# MyNixie.net
KiCad netlist of a schematic drawn in Altium Designer
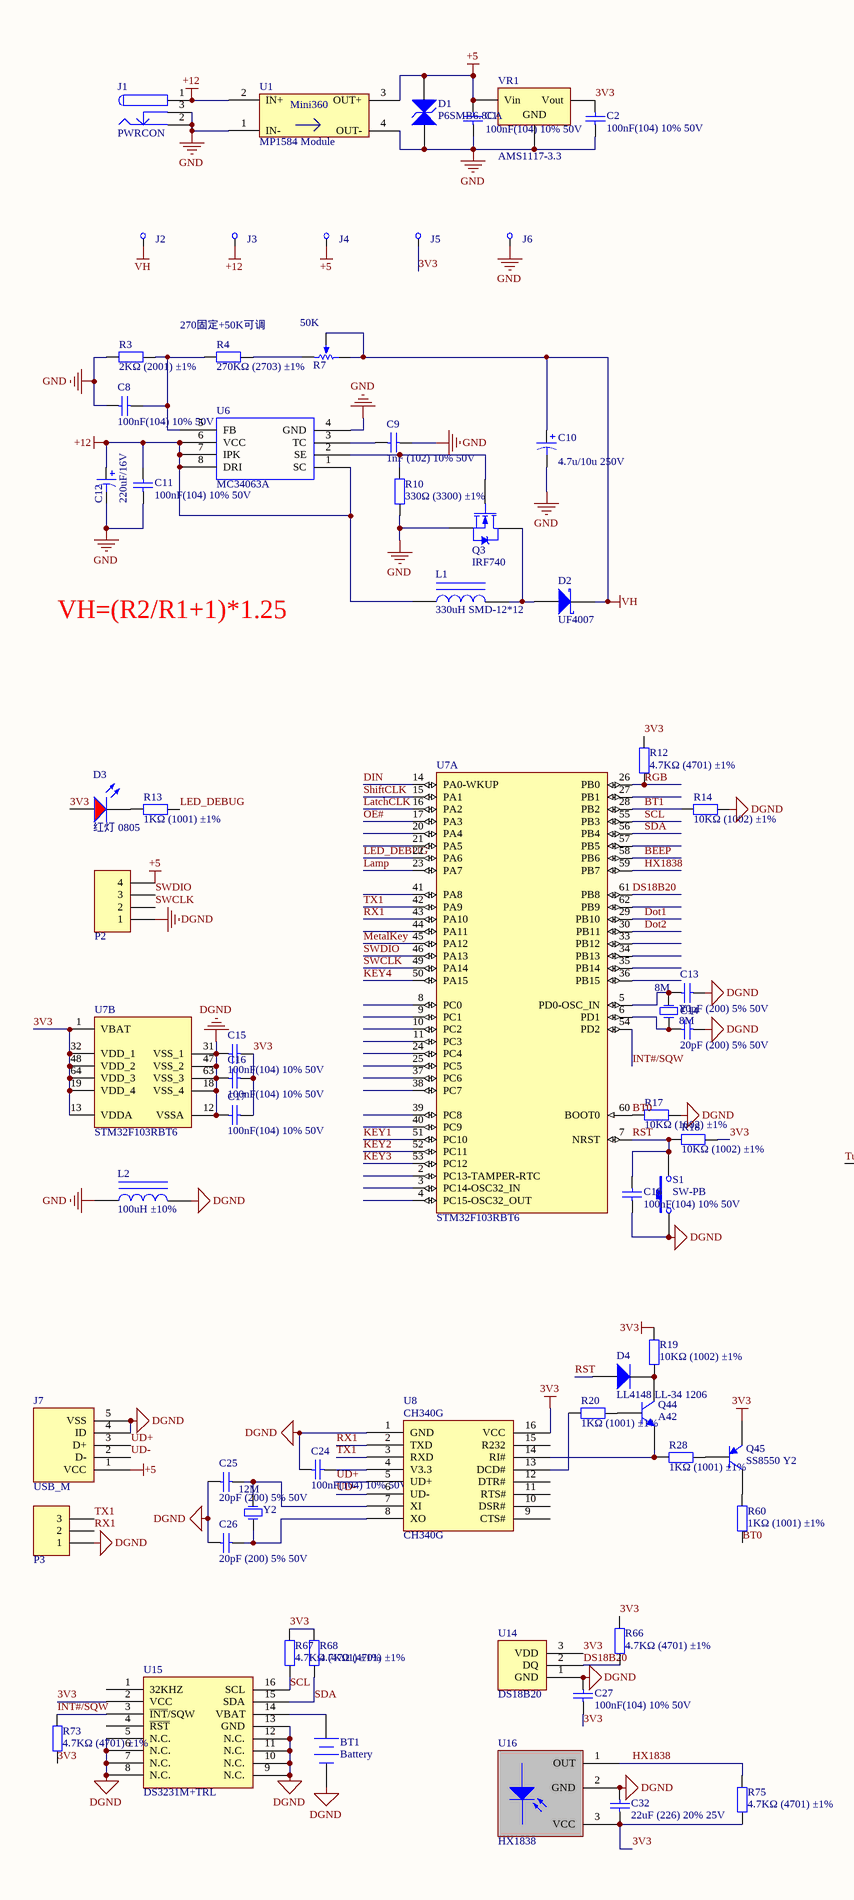
[diagram p0: MyNixie.SchDoc, left]
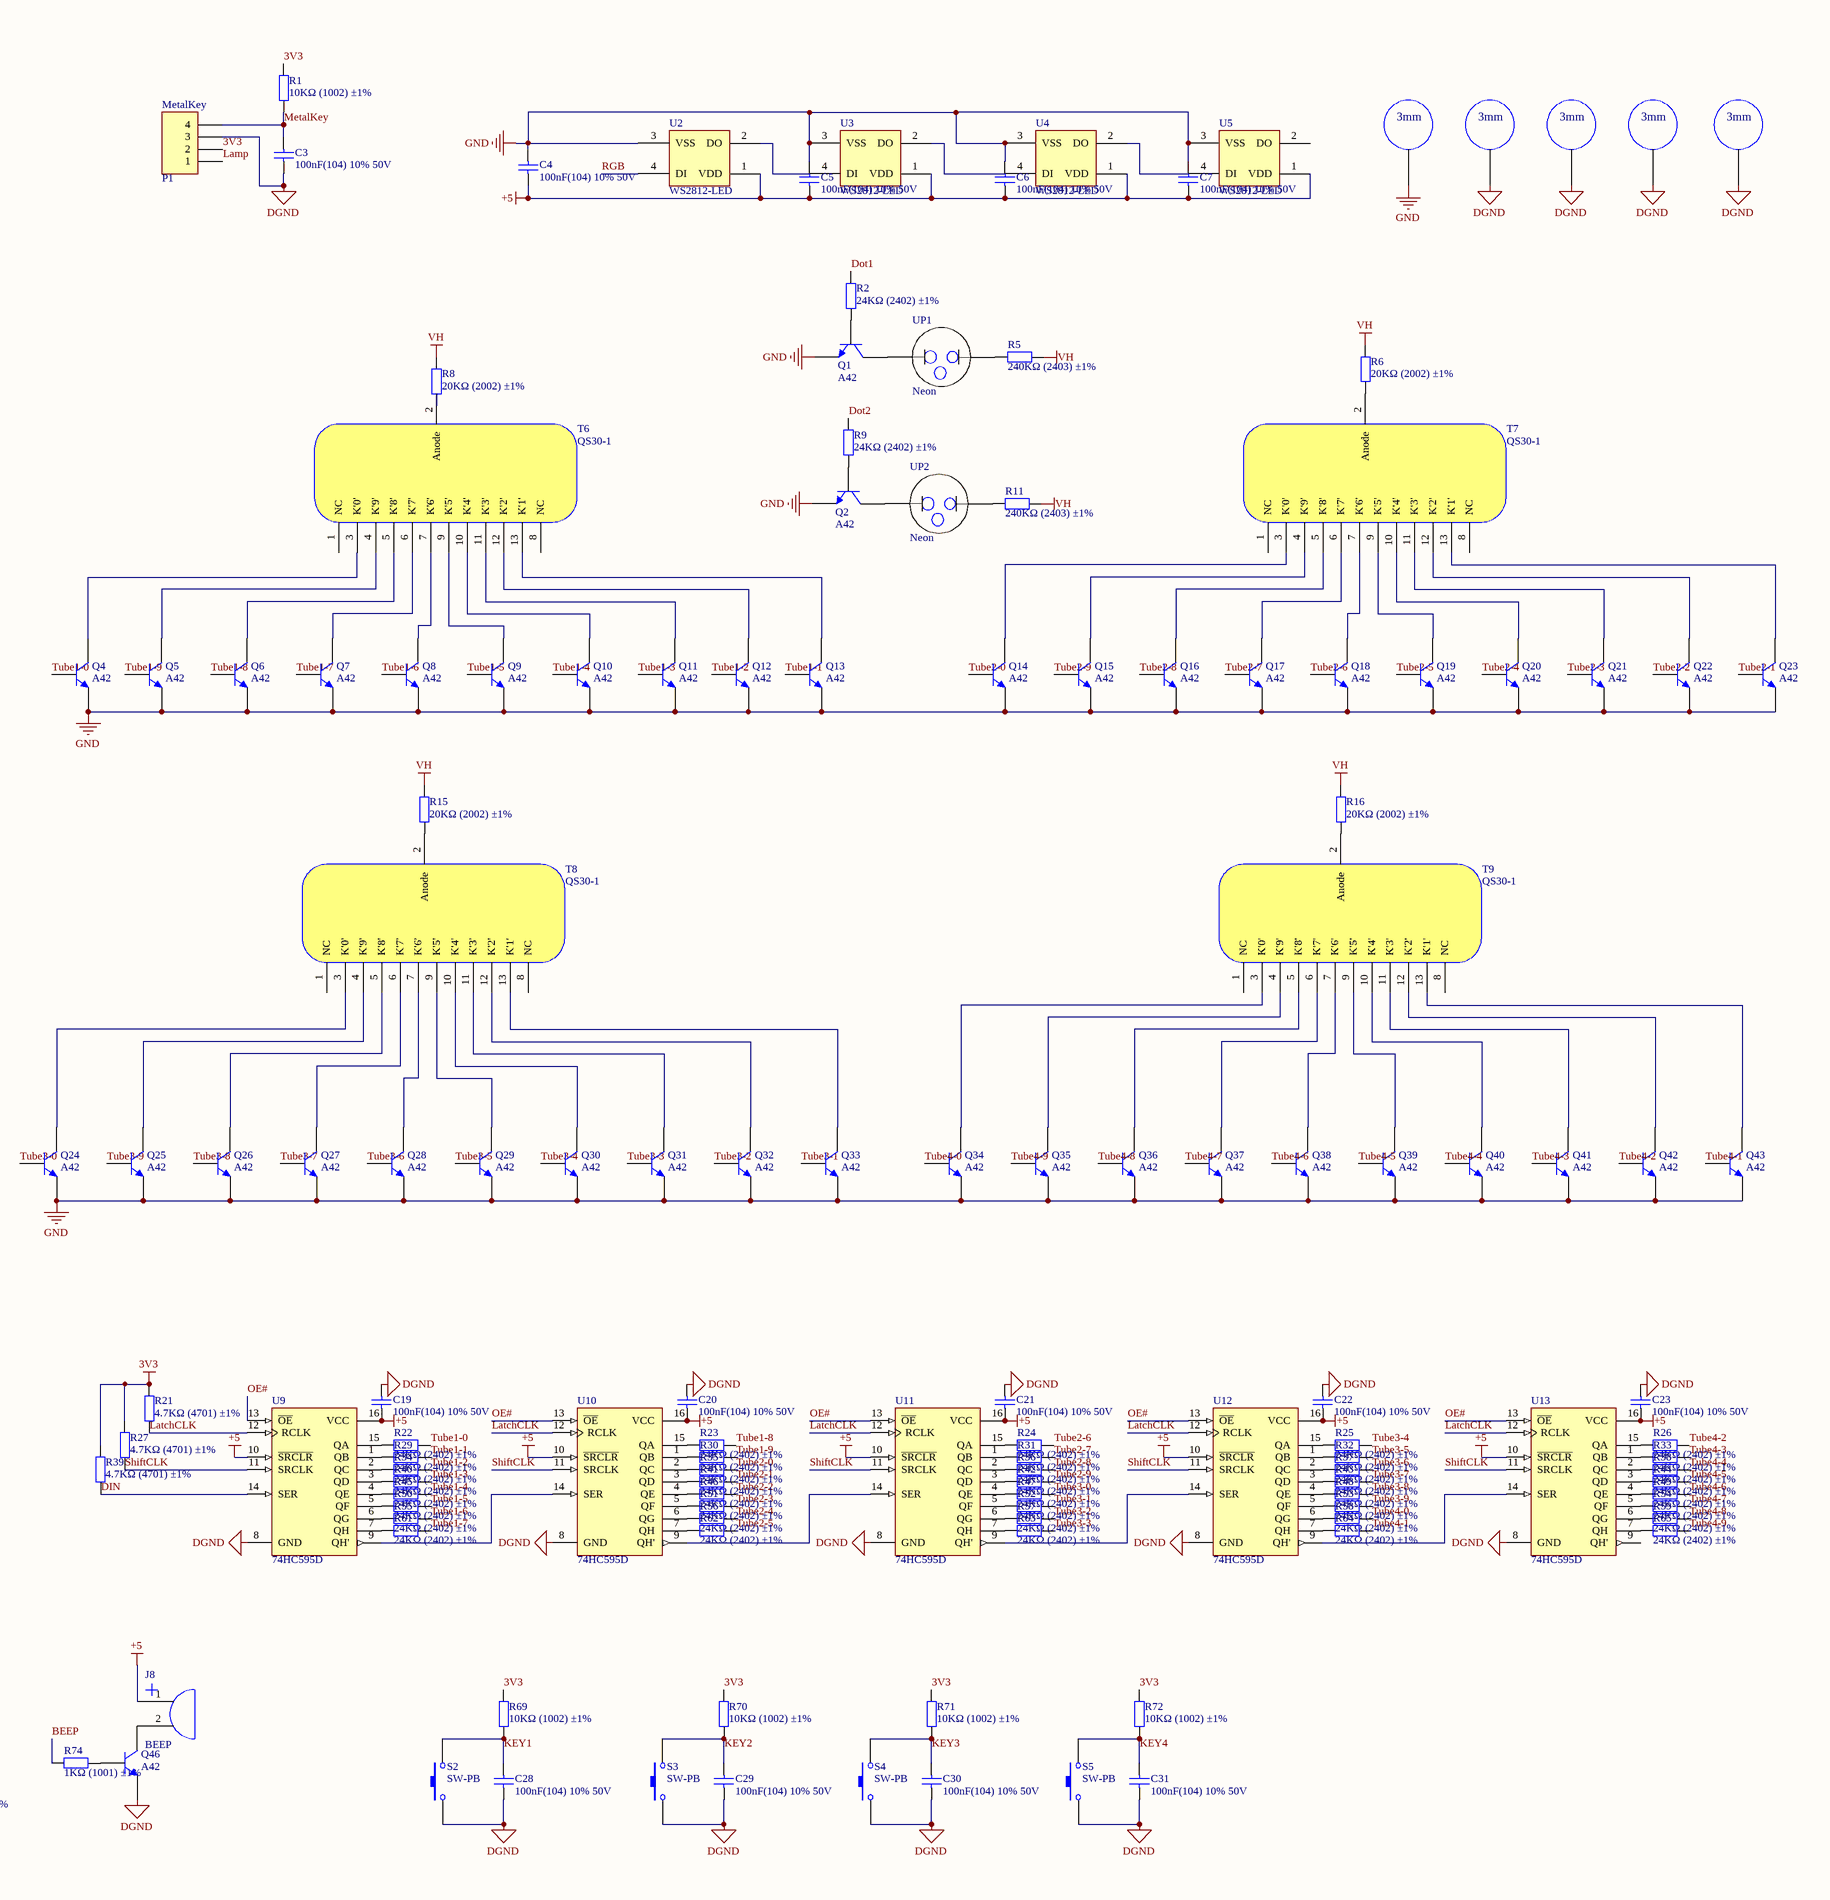
[diagram p1: MyNixie.SchDoc, right]

(export (version "E")
  (design (tool "Eeschema 10.0.6"))
  (components
    (comp (ref "BT1")
      (value "Battery")
      (footprint "CR1220")
      (description "备份电池")
      (fields (field (name "PUBLISHER") "Altium Limited"))
      (libsource (lib "fszhang") (part "Battery"))
    )
    (comp (ref "C1")
      (value "100nF(104) 10% 50V")
      (footprint "0805_C")
      (description "贴片电容")
      (libsource (lib "Miscellaneous Devices LC") (part "0805 100nF(104) 10% 50V"))
    )
    (comp (ref "C2")
      (value "100nF(104) 10% 50V")
      (footprint "0805_C")
      (description "贴片电容")
      (libsource (lib "Miscellaneous Devices LC") (part "0805 100nF(104) 10% 50V"))
    )
    (comp (ref "C3")
      (value "100nF(104) 10% 50V")
      (footprint "0805_C")
      (description "贴片电容")
      (libsource (lib "Miscellaneous Devices LC") (part "0805 100nF(104) 10% 50V"))
    )
    (comp (ref "C4")
      (value "100nF(104) 10% 50V")
      (footprint "0805_C")
      (description "贴片电容")
      (libsource (lib "Miscellaneous Devices LC") (part "0805 100nF(104) 10% 50V"))
    )
    (comp (ref "C5")
      (value "100nF(104) 10% 50V")
      (footprint "0805_C")
      (description "贴片电容")
      (libsource (lib "Miscellaneous Devices LC") (part "0805 100nF(104) 10% 50V"))
    )
    (comp (ref "C6")
      (value "100nF(104) 10% 50V")
      (footprint "0805_C")
      (description "贴片电容")
      (libsource (lib "Miscellaneous Devices LC") (part "0805 100nF(104) 10% 50V"))
    )
    (comp (ref "C7")
      (value "100nF(104) 10% 50V")
      (footprint "0805_C")
      (description "贴片电容")
      (libsource (lib "Miscellaneous Devices LC") (part "0805 100nF(104) 10% 50V"))
    )
    (comp (ref "C8")
      (value "100nF(104) 10% 50V")
      (footprint "0805_C")
      (description "贴片电容")
      (libsource (lib "Miscellaneous Devices LC") (part "0805 100nF(104) 10% 50V"))
    )
    (comp (ref "C9")
      (value "1nF (102) 10% 50V")
      (footprint "0805_C")
      (description "贴片电容")
      (libsource (lib "Miscellaneous Devices LC") (part "0805 1nF (102) 10% 50V"))
    )
    (comp (ref "C10")
      (value "4.7u/10u 250V")
      (footprint "C-RB-8")
      (description "极性电解电容")
      (fields (field (name "PUBLISHER") "Altium Limited"))
      (libsource (lib "Miscellaneous Devices") (part "Cap Pol1"))
    )
    (comp (ref "C11")
      (value "100nF(104) 10% 50V")
      (footprint "0805_C")
      (description "贴片电容")
      (libsource (lib "Miscellaneous Devices LC") (part "0805 100nF(104) 10% 50V"))
    )
    (comp (ref "C12")
      (value "220uF/16V")
      (footprint "C-RB-S6")
      (description "极性电解电容")
      (fields (field (name "PUBLISHER") "Altium Limited"))
      (libsource (lib "Miscellaneous Devices") (part "Cap Pol1"))
    )
    (comp (ref "C13")
      (value "20pF (200) 5% 50V")
      (footprint "0805_C")
      (description "贴片电容")
      (libsource (lib "Miscellaneous Devices LC") (part "0805 20pF (200) 5% 50V"))
    )
    (comp (ref "C14")
      (value "20pF (200) 5% 50V")
      (footprint "0805_C")
      (description "贴片电容")
      (libsource (lib "Miscellaneous Devices LC") (part "0805 20pF (200) 5% 50V"))
    )
    (comp (ref "C15")
      (value "100nF(104) 10% 50V")
      (footprint "0805_C")
      (description "贴片电容")
      (libsource (lib "Miscellaneous Devices LC") (part "0805 100nF(104) 10% 50V"))
    )
    (comp (ref "C16")
      (value "100nF(104) 10% 50V")
      (footprint "0805_C")
      (description "贴片电容")
      (libsource (lib "Miscellaneous Devices LC") (part "0805 100nF(104) 10% 50V"))
    )
    (comp (ref "C17")
      (value "100nF(104) 10% 50V")
      (footprint "0805_C")
      (description "贴片电容")
      (libsource (lib "Miscellaneous Devices LC") (part "0805 100nF(104) 10% 50V"))
    )
    (comp (ref "C18")
      (value "100nF(104) 10% 50V")
      (footprint "0805_C")
      (description "贴片电容")
      (libsource (lib "Miscellaneous Devices LC") (part "0805 100nF(104) 10% 50V"))
    )
    (comp (ref "C19")
      (value "100nF(104) 10% 50V")
      (footprint "0805_C")
      (description "贴片电容")
      (libsource (lib "Miscellaneous Devices LC") (part "0805 100nF(104) 10% 50V"))
    )
    (comp (ref "C20")
      (value "100nF(104) 10% 50V")
      (footprint "0805_C")
      (description "贴片电容")
      (libsource (lib "Miscellaneous Devices LC") (part "0805 100nF(104) 10% 50V"))
    )
    (comp (ref "C21")
      (value "100nF(104) 10% 50V")
      (footprint "0805_C")
      (description "贴片电容")
      (libsource (lib "Miscellaneous Devices LC") (part "0805 100nF(104) 10% 50V"))
    )
    (comp (ref "C22")
      (value "100nF(104) 10% 50V")
      (footprint "0805_C")
      (description "贴片电容")
      (libsource (lib "Miscellaneous Devices LC") (part "0805 100nF(104) 10% 50V"))
    )
    (comp (ref "C23")
      (value "100nF(104) 10% 50V")
      (footprint "0805_C")
      (description "贴片电容")
      (libsource (lib "Miscellaneous Devices LC") (part "0805 100nF(104) 10% 50V"))
    )
    (comp (ref "C24")
      (value "100nF(104) 10% 50V")
      (footprint "0805_C")
      (description "贴片电容")
      (libsource (lib "Miscellaneous Devices LC") (part "0805 100nF(104) 10% 50V"))
    )
    (comp (ref "C25")
      (value "20pF (200) 5% 50V")
      (footprint "0805_C")
      (description "贴片电容")
      (libsource (lib "Miscellaneous Devices LC") (part "0805 20pF (200) 5% 50V"))
    )
    (comp (ref "C26")
      (value "20pF (200) 5% 50V")
      (footprint "0805_C")
      (description "贴片电容")
      (libsource (lib "Miscellaneous Devices LC") (part "0805 20pF (200) 5% 50V"))
    )
    (comp (ref "C27")
      (value "100nF(104) 10% 50V")
      (footprint "0805_C")
      (description "贴片电容")
      (libsource (lib "Miscellaneous Devices LC") (part "0805 100nF(104) 10% 50V"))
    )
    (comp (ref "C28")
      (value "100nF(104) 10% 50V")
      (footprint "0805_C")
      (description "贴片电容")
      (libsource (lib "Miscellaneous Devices LC") (part "0805 100nF(104) 10% 50V"))
    )
    (comp (ref "C29")
      (value "100nF(104) 10% 50V")
      (footprint "0805_C")
      (description "贴片电容")
      (libsource (lib "Miscellaneous Devices LC") (part "0805 100nF(104) 10% 50V"))
    )
    (comp (ref "C30")
      (value "100nF(104) 10% 50V")
      (footprint "0805_C")
      (description "贴片电容")
      (libsource (lib "Miscellaneous Devices LC") (part "0805 100nF(104) 10% 50V"))
    )
    (comp (ref "C31")
      (value "100nF(104) 10% 50V")
      (footprint "0805_C")
      (description "贴片电容")
      (libsource (lib "Miscellaneous Devices LC") (part "0805 100nF(104) 10% 50V"))
    )
    (comp (ref "C32")
      (value "22uF (226) 20% 25V")
      (footprint "0805_C")
      (description "贴片电容")
      (libsource (lib "Miscellaneous Devices LC") (part "0805 22uF (226) 20% 25V"))
    )
    (comp (ref "D1")
      (value "P6SMB6.8CA")
      (footprint "SMB(DO-214AA)_S1")
      (description "TVS")
      (libsource (lib "Miscellaneous Devices LC") (part "SMB/DO-214AA P6SMB6.8CA"))
    )
    (comp (ref "D2")
      (value "UF4007")
      (footprint "SMA(DO-214AC)_S1")
      (description "Schottky Diode")
      (fields (field (name "PUBLISHER") "Altium Limited"))
      (libsource (lib "Miscellaneous Devices") (part "D Schottky"))
    )
    (comp (ref "D3")
      (value "红灯 0805")
      (footprint "0805_LED_S1")
      (description "发光二极管")
      (libsource (lib "Miscellaneous Devices LC") (part "0805 红灯"))
    )
    (comp (ref "D4")
      (value "LL4148 LL-34 1206")
      (footprint "LL-34")
      (description "开关二极管")
      (libsource (lib "Miscellaneous Devices LC") (part "LL-34 LL4148 LL-34 1206"))
    )
    (comp (ref "J1")
      (value "PWRCON")
      (footprint "DC-005")
      (description "直流电源端子")
      (fields (field (name "PUBLISHER") "Altium Limited"))
      (libsource (lib "fszhang") (part "PWRCON"))
    )
    (comp (ref "J2")
      (value "CHECK")
      (footprint "CHECK-B")
      (description "测试点")
      (libsource (lib "fszhang") (part "CHECK"))
    )
    (comp (ref "J3")
      (value "CHECK")
      (footprint "CHECK-B")
      (description "测试点")
      (libsource (lib "fszhang") (part "CHECK"))
    )
    (comp (ref "J4")
      (value "CHECK")
      (footprint "CHECK-B")
      (description "测试点")
      (libsource (lib "fszhang") (part "CHECK"))
    )
    (comp (ref "J5")
      (value "CHECK")
      (footprint "CHECK-B")
      (description "测试点")
      (libsource (lib "fszhang") (part "CHECK"))
    )
    (comp (ref "J6")
      (value "CHECK")
      (footprint "CHECK-B")
      (description "测试点")
      (libsource (lib "fszhang") (part "CHECK"))
    )
    (comp (ref "J7")
      (value "USB_M")
      (footprint "USB_MICRO")
      (description "MicroUSB接口")
      (libsource (lib "fszhang") (part "USB_M"))
    )
    (comp (ref "J8")
      (value "BEEP")
      (footprint "Beep-12095")
      (description "蜂鸣器")
      (libsource (lib "fszhang") (part "BEEP"))
    )
    (comp (ref "L1")
      (value "330uH SMD-12*12")
      (footprint "L-SMD-12")
      (description "Magnetic-Core Inductor")
      (fields (field (name "PUBLISHER") "Altium Limited"))
      (libsource (lib "Miscellaneous Devices") (part "Inductor Iron"))
    )
    (comp (ref "L2")
      (value "100uH ±10%")
      (footprint "0805_L")
      (description "贴片电感")
      (libsource (lib "Miscellaneous Devices LC") (part "0805 100uH 10%"))
    )
    (comp (ref "P1")
      (value "MetalKey")
      (footprint "HDR4X1_A")
      (description "接插件")
      (fields (field (name "PUBLISHER") "Altium Limited"))
      (libsource (lib "fszhang") (part "Header 4"))
    )
    (comp (ref "P2")
      (value "Header 4")
      (footprint "HDR4X1_A")
      (description "接插件")
      (fields (field (name "PUBLISHER") "Altium Limited"))
      (libsource (lib "fszhang") (part "Header 4"))
    )
    (comp (ref "P3")
      (value "Header 3")
      (footprint "HDR3X1_A")
      (description "接插件")
      (fields (field (name "PUBLISHER") "Altium Limited"))
      (libsource (lib "fszhang") (part "Header 3"))
    )
    (comp (ref "Q1")
      (value "A42")
      (footprint "SOT-23(SOT-23-3)")
      (description "三极管")
      (libsource (lib "Miscellaneous Devices LC") (part "SOT-23 SS8050 Y1"))
    )
    (comp (ref "Q2")
      (value "A42")
      (footprint "SOT-23(SOT-23-3)")
      (description "三极管")
      (libsource (lib "Miscellaneous Devices LC") (part "SOT-23 SS8050 Y1"))
    )
    (comp (ref "Q3")
      (value "IRF740")
      (footprint "Miscellaneous Devices LC:TO-263-2")
      (description "N-Channel Power MOSFET")
      (fields (field (name "PUBLISHER") "Altium Limited"))
      (libsource (lib "Miscellaneous Devices") (part "NMOS-2"))
    )
    (comp (ref "Q4")
      (value "A42")
      (footprint "SOT-23(SOT-23-3)")
      (description "三极管")
      (libsource (lib "Miscellaneous Devices LC") (part "SOT-23 SS8050 Y1"))
    )
    (comp (ref "Q5")
      (value "A42")
      (footprint "SOT-23(SOT-23-3)")
      (description "三极管")
      (libsource (lib "Miscellaneous Devices LC") (part "SOT-23 SS8050 Y1"))
    )
    (comp (ref "Q6")
      (value "A42")
      (footprint "SOT-23(SOT-23-3)")
      (description "三极管")
      (libsource (lib "Miscellaneous Devices LC") (part "SOT-23 SS8050 Y1"))
    )
    (comp (ref "Q7")
      (value "A42")
      (footprint "SOT-23(SOT-23-3)")
      (description "三极管")
      (libsource (lib "Miscellaneous Devices LC") (part "SOT-23 SS8050 Y1"))
    )
    (comp (ref "Q8")
      (value "A42")
      (footprint "SOT-23(SOT-23-3)")
      (description "三极管")
      (libsource (lib "Miscellaneous Devices LC") (part "SOT-23 SS8050 Y1"))
    )
    (comp (ref "Q9")
      (value "A42")
      (footprint "SOT-23(SOT-23-3)")
      (description "三极管")
      (libsource (lib "Miscellaneous Devices LC") (part "SOT-23 SS8050 Y1"))
    )
    (comp (ref "Q10")
      (value "A42")
      (footprint "SOT-23(SOT-23-3)")
      (description "三极管")
      (libsource (lib "Miscellaneous Devices LC") (part "SOT-23 SS8050 Y1"))
    )
    (comp (ref "Q11")
      (value "A42")
      (footprint "SOT-23(SOT-23-3)")
      (description "三极管")
      (libsource (lib "Miscellaneous Devices LC") (part "SOT-23 SS8050 Y1"))
    )
    (comp (ref "Q12")
      (value "A42")
      (footprint "SOT-23(SOT-23-3)")
      (description "三极管")
      (libsource (lib "Miscellaneous Devices LC") (part "SOT-23 SS8050 Y1"))
    )
    (comp (ref "Q13")
      (value "A42")
      (footprint "SOT-23(SOT-23-3)")
      (description "三极管")
      (libsource (lib "Miscellaneous Devices LC") (part "SOT-23 SS8050 Y1"))
    )
    (comp (ref "Q14")
      (value "A42")
      (footprint "SOT-23(SOT-23-3)")
      (description "三极管")
      (libsource (lib "Miscellaneous Devices LC") (part "SOT-23 SS8050 Y1"))
    )
    (comp (ref "Q15")
      (value "A42")
      (footprint "SOT-23(SOT-23-3)")
      (description "三极管")
      (libsource (lib "Miscellaneous Devices LC") (part "SOT-23 SS8050 Y1"))
    )
    (comp (ref "Q16")
      (value "A42")
      (footprint "SOT-23(SOT-23-3)")
      (description "三极管")
      (libsource (lib "Miscellaneous Devices LC") (part "SOT-23 SS8050 Y1"))
    )
    (comp (ref "Q17")
      (value "A42")
      (footprint "SOT-23(SOT-23-3)")
      (description "三极管")
      (libsource (lib "Miscellaneous Devices LC") (part "SOT-23 SS8050 Y1"))
    )
    (comp (ref "Q18")
      (value "A42")
      (footprint "SOT-23(SOT-23-3)")
      (description "三极管")
      (libsource (lib "Miscellaneous Devices LC") (part "SOT-23 SS8050 Y1"))
    )
    (comp (ref "Q19")
      (value "A42")
      (footprint "SOT-23(SOT-23-3)")
      (description "三极管")
      (libsource (lib "Miscellaneous Devices LC") (part "SOT-23 SS8050 Y1"))
    )
    (comp (ref "Q20")
      (value "A42")
      (footprint "SOT-23(SOT-23-3)")
      (description "三极管")
      (libsource (lib "Miscellaneous Devices LC") (part "SOT-23 SS8050 Y1"))
    )
    (comp (ref "Q21")
      (value "A42")
      (footprint "SOT-23(SOT-23-3)")
      (description "三极管")
      (libsource (lib "Miscellaneous Devices LC") (part "SOT-23 SS8050 Y1"))
    )
    (comp (ref "Q22")
      (value "A42")
      (footprint "SOT-23(SOT-23-3)")
      (description "三极管")
      (libsource (lib "Miscellaneous Devices LC") (part "SOT-23 SS8050 Y1"))
    )
    (comp (ref "Q23")
      (value "A42")
      (footprint "SOT-23(SOT-23-3)")
      (description "三极管")
      (libsource (lib "Miscellaneous Devices LC") (part "SOT-23 SS8050 Y1"))
    )
    (comp (ref "Q24")
      (value "A42")
      (footprint "SOT-23(SOT-23-3)")
      (description "三极管")
      (libsource (lib "Miscellaneous Devices LC") (part "SOT-23 SS8050 Y1"))
    )
    (comp (ref "Q25")
      (value "A42")
      (footprint "SOT-23(SOT-23-3)")
      (description "三极管")
      (libsource (lib "Miscellaneous Devices LC") (part "SOT-23 SS8050 Y1"))
    )
    (comp (ref "Q26")
      (value "A42")
      (footprint "SOT-23(SOT-23-3)")
      (description "三极管")
      (libsource (lib "Miscellaneous Devices LC") (part "SOT-23 SS8050 Y1"))
    )
    (comp (ref "Q27")
      (value "A42")
      (footprint "SOT-23(SOT-23-3)")
      (description "三极管")
      (libsource (lib "Miscellaneous Devices LC") (part "SOT-23 SS8050 Y1"))
    )
    (comp (ref "Q28")
      (value "A42")
      (footprint "SOT-23(SOT-23-3)")
      (description "三极管")
      (libsource (lib "Miscellaneous Devices LC") (part "SOT-23 SS8050 Y1"))
    )
    (comp (ref "Q29")
      (value "A42")
      (footprint "SOT-23(SOT-23-3)")
      (description "三极管")
      (libsource (lib "Miscellaneous Devices LC") (part "SOT-23 SS8050 Y1"))
    )
    (comp (ref "Q30")
      (value "A42")
      (footprint "SOT-23(SOT-23-3)")
      (description "三极管")
      (libsource (lib "Miscellaneous Devices LC") (part "SOT-23 SS8050 Y1"))
    )
    (comp (ref "Q31")
      (value "A42")
      (footprint "SOT-23(SOT-23-3)")
      (description "三极管")
      (libsource (lib "Miscellaneous Devices LC") (part "SOT-23 SS8050 Y1"))
    )
    (comp (ref "Q32")
      (value "A42")
      (footprint "SOT-23(SOT-23-3)")
      (description "三极管")
      (libsource (lib "Miscellaneous Devices LC") (part "SOT-23 SS8050 Y1"))
    )
    (comp (ref "Q33")
      (value "A42")
      (footprint "SOT-23(SOT-23-3)")
      (description "三极管")
      (libsource (lib "Miscellaneous Devices LC") (part "SOT-23 SS8050 Y1"))
    )
    (comp (ref "Q34")
      (value "A42")
      (footprint "SOT-23(SOT-23-3)")
      (description "三极管")
      (libsource (lib "Miscellaneous Devices LC") (part "SOT-23 SS8050 Y1"))
    )
    (comp (ref "Q35")
      (value "A42")
      (footprint "SOT-23(SOT-23-3)")
      (description "三极管")
      (libsource (lib "Miscellaneous Devices LC") (part "SOT-23 SS8050 Y1"))
    )
    (comp (ref "Q36")
      (value "A42")
      (footprint "SOT-23(SOT-23-3)")
      (description "三极管")
      (libsource (lib "Miscellaneous Devices LC") (part "SOT-23 SS8050 Y1"))
    )
    (comp (ref "Q37")
      (value "A42")
      (footprint "SOT-23(SOT-23-3)")
      (description "三极管")
      (libsource (lib "Miscellaneous Devices LC") (part "SOT-23 SS8050 Y1"))
    )
    (comp (ref "Q38")
      (value "A42")
      (footprint "SOT-23(SOT-23-3)")
      (description "三极管")
      (libsource (lib "Miscellaneous Devices LC") (part "SOT-23 SS8050 Y1"))
    )
    (comp (ref "Q39")
      (value "A42")
      (footprint "SOT-23(SOT-23-3)")
      (description "三极管")
      (libsource (lib "Miscellaneous Devices LC") (part "SOT-23 SS8050 Y1"))
    )
    (comp (ref "Q40")
      (value "A42")
      (footprint "SOT-23(SOT-23-3)")
      (description "三极管")
      (libsource (lib "Miscellaneous Devices LC") (part "SOT-23 SS8050 Y1"))
    )
    (comp (ref "Q41")
      (value "A42")
      (footprint "SOT-23(SOT-23-3)")
      (description "三极管")
      (libsource (lib "Miscellaneous Devices LC") (part "SOT-23 SS8050 Y1"))
    )
    (comp (ref "Q42")
      (value "A42")
      (footprint "SOT-23(SOT-23-3)")
      (description "三极管")
      (libsource (lib "Miscellaneous Devices LC") (part "SOT-23 SS8050 Y1"))
    )
    (comp (ref "Q43")
      (value "A42")
      (footprint "SOT-23(SOT-23-3)")
      (description "三极管")
      (libsource (lib "Miscellaneous Devices LC") (part "SOT-23 SS8050 Y1"))
    )
    (comp (ref "Q44")
      (value "A42")
      (footprint "SOT-23(SOT-23-3)")
      (description "三极管")
      (libsource (lib "Miscellaneous Devices LC") (part "SOT-23 SS8050 Y1"))
    )
    (comp (ref "Q45")
      (value "SS8550 Y2")
      (footprint "SOT-23(SOT-23-3)")
      (description "三极管")
      (libsource (lib "Miscellaneous Devices LC") (part "SOT-23 SS8550 Y2"))
    )
    (comp (ref "Q46")
      (value "A42")
      (footprint "SOT-23(SOT-23-3)")
      (description "三极管")
      (libsource (lib "Miscellaneous Devices LC") (part "SOT-23 SS8050 Y1"))
    )
    (comp (ref "R1")
      (value "10KΩ (1002) ±1%")
      (footprint "0805_R")
      (description "贴片电阻")
      (libsource (lib "Miscellaneous Devices LC") (part "0805 10KΩ (1002) 1%"))
    )
    (comp (ref "R2")
      (value "24KΩ (2402) ±1%")
      (footprint "0805_R")
      (description "贴片电阻")
      (libsource (lib "") (part "0805 24KΩ (2402) 1%_1"))
    )
    (comp (ref "R3")
      (value "2KΩ (2001) ±1%")
      (footprint "0805_R")
      (description "贴片电阻")
      (libsource (lib "Miscellaneous Devices LC") (part "0805 2KΩ (2001) 1%"))
    )
    (comp (ref "R4")
      (value "270KΩ (2703) ±1%")
      (footprint "0805_R")
      (description "贴片电阻")
      (libsource (lib "Miscellaneous Devices LC") (part "0805 270KΩ (2703) 1%"))
    )
    (comp (ref "R5")
      (value "240KΩ (2403) ±1%")
      (footprint "0805_R")
      (description "贴片电阻")
      (libsource (lib "Miscellaneous Devices LC") (part "0805 240KΩ (2403) 1%"))
    )
    (comp (ref "R6")
      (value "20KΩ (2002) ±1%")
      (footprint "0805_R")
      (description "贴片电阻")
      (libsource (lib "Miscellaneous Devices LC") (part "0805 20KΩ (2002) 1%"))
    )
    (comp (ref "R7")
      (value "50K")
      (footprint "VR_B1")
      (description "精密可调电阻")
      (fields (field (name "PUBLISHER") "Altium Limited"))
      (libsource (lib "fszhang") (part "RES-RPot"))
    )
    (comp (ref "R8")
      (value "20KΩ (2002) ±1%")
      (footprint "0805_R")
      (description "贴片电阻")
      (libsource (lib "Miscellaneous Devices LC") (part "0805 20KΩ (2002) 1%"))
    )
    (comp (ref "R9")
      (value "24KΩ (2402) ±1%")
      (footprint "0805_R")
      (description "贴片电阻")
      (libsource (lib "") (part "0805 24KΩ (2402) 1%_1"))
    )
    (comp (ref "R10")
      (value "330Ω (3300) ±1%")
      (footprint "0805_R")
      (description "贴片电阻")
      (libsource (lib "Miscellaneous Devices LC") (part "0805 330Ω (3300) 1%"))
    )
    (comp (ref "R11")
      (value "240KΩ (2403) ±1%")
      (footprint "0805_R")
      (description "贴片电阻")
      (libsource (lib "Miscellaneous Devices LC") (part "0805 240KΩ (2403) 1%"))
    )
    (comp (ref "R12")
      (value "4.7KΩ (4701) ±1%")
      (footprint "0805_R")
      (description "贴片电阻")
      (libsource (lib "Miscellaneous Devices LC") (part "0805 4.7KΩ (4701) 1%"))
    )
    (comp (ref "R13")
      (value "1KΩ (1001) ±1%")
      (footprint "0805_R")
      (description "贴片电阻")
      (libsource (lib "Miscellaneous Devices LC") (part "0805 1KΩ (1001) 1%"))
    )
    (comp (ref "R14")
      (value "10KΩ (1002) ±1%")
      (footprint "0805_R")
      (description "贴片电阻")
      (libsource (lib "") (part "0805 10KΩ (1002) 1%_1"))
    )
    (comp (ref "R15")
      (value "20KΩ (2002) ±1%")
      (footprint "0805_R")
      (description "贴片电阻")
      (libsource (lib "Miscellaneous Devices LC") (part "0805 20KΩ (2002) 1%"))
    )
    (comp (ref "R16")
      (value "20KΩ (2002) ±1%")
      (footprint "0805_R")
      (description "贴片电阻")
      (libsource (lib "Miscellaneous Devices LC") (part "0805 20KΩ (2002) 1%"))
    )
    (comp (ref "R17")
      (value "10KΩ (1002) ±1%")
      (footprint "0805_R")
      (description "贴片电阻")
      (libsource (lib "") (part "0805 10KΩ (1002) 1%_1"))
    )
    (comp (ref "R18")
      (value "10KΩ (1002) ±1%")
      (footprint "0805_R")
      (description "贴片电阻")
      (libsource (lib "") (part "0805 10KΩ (1002) 1%_1"))
    )
    (comp (ref "R19")
      (value "10KΩ (1002) ±1%")
      (footprint "0805_R")
      (description "贴片电阻")
      (libsource (lib "") (part "0805 10KΩ (1002) 1%_2"))
    )
    (comp (ref "R20")
      (value "1KΩ (1001) ±1%")
      (footprint "0805_R")
      (description "贴片电阻")
      (libsource (lib "Miscellaneous Devices LC") (part "0805 1KΩ (1001) 1%"))
    )
    (comp (ref "R21")
      (value "4.7KΩ (4701) ±1%")
      (footprint "0805_R")
      (description "贴片电阻")
      (libsource (lib "") (part "0805 4.7KΩ (4701) 1%_1"))
    )
    (comp (ref "R22")
      (value "24KΩ (2402) ±1%")
      (footprint "0805_R")
      (description "贴片电阻")
      (libsource (lib "Miscellaneous Devices LC") (part "0805 24KΩ (2402) 1%"))
    )
    (comp (ref "R23")
      (value "24KΩ (2402) ±1%")
      (footprint "0805_R")
      (description "贴片电阻")
      (libsource (lib "Miscellaneous Devices LC") (part "0805 24KΩ (2402) 1%"))
    )
    (comp (ref "R24")
      (value "24KΩ (2402) ±1%")
      (footprint "0805_R")
      (description "贴片电阻")
      (libsource (lib "Miscellaneous Devices LC") (part "0805 24KΩ (2402) 1%"))
    )
    (comp (ref "R25")
      (value "24KΩ (2402) ±1%")
      (footprint "0805_R")
      (description "贴片电阻")
      (libsource (lib "Miscellaneous Devices LC") (part "0805 24KΩ (2402) 1%"))
    )
    (comp (ref "R26")
      (value "24KΩ (2402) ±1%")
      (footprint "0805_R")
      (description "贴片电阻")
      (libsource (lib "Miscellaneous Devices LC") (part "0805 24KΩ (2402) 1%"))
    )
    (comp (ref "R27")
      (value "4.7KΩ (4701) ±1%")
      (footprint "0805_R")
      (description "贴片电阻")
      (libsource (lib "") (part "0805 4.7KΩ (4701) 1%_1"))
    )
    (comp (ref "R28")
      (value "1KΩ (1001) ±1%")
      (footprint "0805_R")
      (description "贴片电阻")
      (libsource (lib "Miscellaneous Devices LC") (part "0805 1KΩ (1001) 1%"))
    )
    (comp (ref "R29")
      (value "24KΩ (2402) ±1%")
      (footprint "0805_R")
      (description "贴片电阻")
      (libsource (lib "Miscellaneous Devices LC") (part "0805 24KΩ (2402) 1%"))
    )
    (comp (ref "R30")
      (value "24KΩ (2402) ±1%")
      (footprint "0805_R")
      (description "贴片电阻")
      (libsource (lib "Miscellaneous Devices LC") (part "0805 24KΩ (2402) 1%"))
    )
    (comp (ref "R31")
      (value "24KΩ (2402) ±1%")
      (footprint "0805_R")
      (description "贴片电阻")
      (libsource (lib "Miscellaneous Devices LC") (part "0805 24KΩ (2402) 1%"))
    )
    (comp (ref "R32")
      (value "24KΩ (2402) ±1%")
      (footprint "0805_R")
      (description "贴片电阻")
      (libsource (lib "Miscellaneous Devices LC") (part "0805 24KΩ (2402) 1%"))
    )
    (comp (ref "R33")
      (value "24KΩ (2402) ±1%")
      (footprint "0805_R")
      (description "贴片电阻")
      (libsource (lib "Miscellaneous Devices LC") (part "0805 24KΩ (2402) 1%"))
    )
    (comp (ref "R34")
      (value "24KΩ (2402) ±1%")
      (footprint "0805_R")
      (description "贴片电阻")
      (libsource (lib "Miscellaneous Devices LC") (part "0805 24KΩ (2402) 1%"))
    )
    (comp (ref "R35")
      (value "24KΩ (2402) ±1%")
      (footprint "0805_R")
      (description "贴片电阻")
      (libsource (lib "Miscellaneous Devices LC") (part "0805 24KΩ (2402) 1%"))
    )
    (comp (ref "R36")
      (value "24KΩ (2402) ±1%")
      (footprint "0805_R")
      (description "贴片电阻")
      (libsource (lib "Miscellaneous Devices LC") (part "0805 24KΩ (2402) 1%"))
    )
    (comp (ref "R37")
      (value "24KΩ (2402) ±1%")
      (footprint "0805_R")
      (description "贴片电阻")
      (libsource (lib "Miscellaneous Devices LC") (part "0805 24KΩ (2402) 1%"))
    )
    (comp (ref "R38")
      (value "24KΩ (2402) ±1%")
      (footprint "0805_R")
      (description "贴片电阻")
      (libsource (lib "Miscellaneous Devices LC") (part "0805 24KΩ (2402) 1%"))
    )
    (comp (ref "R39")
      (value "4.7KΩ (4701) ±1%")
      (footprint "0805_R")
      (description "贴片电阻")
      (libsource (lib "") (part "0805 4.7KΩ (4701) 1%_1"))
    )
    (comp (ref "R40")
      (value "24KΩ (2402) ±1%")
      (footprint "0805_R")
      (description "贴片电阻")
      (libsource (lib "Miscellaneous Devices LC") (part "0805 24KΩ (2402) 1%"))
    )
    (comp (ref "R41")
      (value "24KΩ (2402) ±1%")
      (footprint "0805_R")
      (description "贴片电阻")
      (libsource (lib "Miscellaneous Devices LC") (part "0805 24KΩ (2402) 1%"))
    )
    (comp (ref "R42")
      (value "24KΩ (2402) ±1%")
      (footprint "0805_R")
      (description "贴片电阻")
      (libsource (lib "Miscellaneous Devices LC") (part "0805 24KΩ (2402) 1%"))
    )
    (comp (ref "R43")
      (value "24KΩ (2402) ±1%")
      (footprint "0805_R")
      (description "贴片电阻")
      (libsource (lib "Miscellaneous Devices LC") (part "0805 24KΩ (2402) 1%"))
    )
    (comp (ref "R44")
      (value "24KΩ (2402) ±1%")
      (footprint "0805_R")
      (description "贴片电阻")
      (libsource (lib "Miscellaneous Devices LC") (part "0805 24KΩ (2402) 1%"))
    )
    (comp (ref "R45")
      (value "24KΩ (2402) ±1%")
      (footprint "0805_R")
      (description "贴片电阻")
      (libsource (lib "Miscellaneous Devices LC") (part "0805 24KΩ (2402) 1%"))
    )
    (comp (ref "R46")
      (value "24KΩ (2402) ±1%")
      (footprint "0805_R")
      (description "贴片电阻")
      (libsource (lib "Miscellaneous Devices LC") (part "0805 24KΩ (2402) 1%"))
    )
    (comp (ref "R47")
      (value "24KΩ (2402) ±1%")
      (footprint "0805_R")
      (description "贴片电阻")
      (libsource (lib "Miscellaneous Devices LC") (part "0805 24KΩ (2402) 1%"))
    )
    (comp (ref "R48")
      (value "24KΩ (2402) ±1%")
      (footprint "0805_R")
      (description "贴片电阻")
      (libsource (lib "Miscellaneous Devices LC") (part "0805 24KΩ (2402) 1%"))
    )
    (comp (ref "R49")
      (value "24KΩ (2402) ±1%")
      (footprint "0805_R")
      (description "贴片电阻")
      (libsource (lib "Miscellaneous Devices LC") (part "0805 24KΩ (2402) 1%"))
    )
    (comp (ref "R50")
      (value "24KΩ (2402) ±1%")
      (footprint "0805_R")
      (description "贴片电阻")
      (libsource (lib "Miscellaneous Devices LC") (part "0805 24KΩ (2402) 1%"))
    )
    (comp (ref "R51")
      (value "24KΩ (2402) ±1%")
      (footprint "0805_R")
      (description "贴片电阻")
      (libsource (lib "Miscellaneous Devices LC") (part "0805 24KΩ (2402) 1%"))
    )
    (comp (ref "R52")
      (value "24KΩ (2402) ±1%")
      (footprint "0805_R")
      (description "贴片电阻")
      (libsource (lib "Miscellaneous Devices LC") (part "0805 24KΩ (2402) 1%"))
    )
    (comp (ref "R53")
      (value "24KΩ (2402) ±1%")
      (footprint "0805_R")
      (description "贴片电阻")
      (libsource (lib "Miscellaneous Devices LC") (part "0805 24KΩ (2402) 1%"))
    )
    (comp (ref "R54")
      (value "24KΩ (2402) ±1%")
      (footprint "0805_R")
      (description "贴片电阻")
      (libsource (lib "Miscellaneous Devices LC") (part "0805 24KΩ (2402) 1%"))
    )
    (comp (ref "R55")
      (value "24KΩ (2402) ±1%")
      (footprint "0805_R")
      (description "贴片电阻")
      (libsource (lib "Miscellaneous Devices LC") (part "0805 24KΩ (2402) 1%"))
    )
    (comp (ref "R56")
      (value "24KΩ (2402) ±1%")
      (footprint "0805_R")
      (description "贴片电阻")
      (libsource (lib "Miscellaneous Devices LC") (part "0805 24KΩ (2402) 1%"))
    )
    (comp (ref "R57")
      (value "24KΩ (2402) ±1%")
      (footprint "0805_R")
      (description "贴片电阻")
      (libsource (lib "Miscellaneous Devices LC") (part "0805 24KΩ (2402) 1%"))
    )
    (comp (ref "R58")
      (value "24KΩ (2402) ±1%")
      (footprint "0805_R")
      (description "贴片电阻")
      (libsource (lib "Miscellaneous Devices LC") (part "0805 24KΩ (2402) 1%"))
    )
    (comp (ref "R59")
      (value "24KΩ (2402) ±1%")
      (footprint "0805_R")
      (description "贴片电阻")
      (libsource (lib "Miscellaneous Devices LC") (part "0805 24KΩ (2402) 1%"))
    )
    (comp (ref "R60")
      (value "1KΩ (1001) ±1%")
      (footprint "0805_R")
      (description "贴片电阻")
      (libsource (lib "") (part "0805 1KΩ (1001) 1%_1"))
    )
    (comp (ref "R61")
      (value "24KΩ (2402) ±1%")
      (footprint "0805_R")
      (description "贴片电阻")
      (libsource (lib "Miscellaneous Devices LC") (part "0805 24KΩ (2402) 1%"))
    )
    (comp (ref "R62")
      (value "24KΩ (2402) ±1%")
      (footprint "0805_R")
      (description "贴片电阻")
      (libsource (lib "Miscellaneous Devices LC") (part "0805 24KΩ (2402) 1%"))
    )
    (comp (ref "R63")
      (value "24KΩ (2402) ±1%")
      (footprint "0805_R")
      (description "贴片电阻")
      (libsource (lib "Miscellaneous Devices LC") (part "0805 24KΩ (2402) 1%"))
    )
    (comp (ref "R64")
      (value "24KΩ (2402) ±1%")
      (footprint "0805_R")
      (description "贴片电阻")
      (libsource (lib "Miscellaneous Devices LC") (part "0805 24KΩ (2402) 1%"))
    )
    (comp (ref "R65")
      (value "24KΩ (2402) ±1%")
      (footprint "0805_R")
      (description "贴片电阻")
      (libsource (lib "Miscellaneous Devices LC") (part "0805 24KΩ (2402) 1%"))
    )
    (comp (ref "R66")
      (value "4.7KΩ (4701) ±1%")
      (footprint "0805_R")
      (description "贴片电阻")
      (libsource (lib "Miscellaneous Devices LC") (part "0805 4.7KΩ (4701) 1%"))
    )
    (comp (ref "R67")
      (value "4.7KΩ (4701) ±1%")
      (footprint "0805_R")
      (description "贴片电阻")
      (libsource (lib "Miscellaneous Devices LC") (part "0805 4.7KΩ (4701) 1%"))
    )
    (comp (ref "R68")
      (value "4.7KΩ (4701) ±1%")
      (footprint "0805_R")
      (description "贴片电阻")
      (libsource (lib "Miscellaneous Devices LC") (part "0805 4.7KΩ (4701) 1%"))
    )
    (comp (ref "R69")
      (value "10KΩ (1002) ±1%")
      (footprint "0805_R")
      (description "贴片电阻")
      (libsource (lib "Miscellaneous Devices LC") (part "0805 10KΩ (1002) 1%"))
    )
    (comp (ref "R70")
      (value "10KΩ (1002) ±1%")
      (footprint "0805_R")
      (description "贴片电阻")
      (libsource (lib "Miscellaneous Devices LC") (part "0805 10KΩ (1002) 1%"))
    )
    (comp (ref "R71")
      (value "10KΩ (1002) ±1%")
      (footprint "0805_R")
      (description "贴片电阻")
      (libsource (lib "Miscellaneous Devices LC") (part "0805 10KΩ (1002) 1%"))
    )
    (comp (ref "R72")
      (value "10KΩ (1002) ±1%")
      (footprint "0805_R")
      (description "贴片电阻")
      (libsource (lib "Miscellaneous Devices LC") (part "0805 10KΩ (1002) 1%"))
    )
    (comp (ref "R73")
      (value "4.7KΩ (4701) ±1%")
      (footprint "0805_R")
      (description "贴片电阻")
      (libsource (lib "Miscellaneous Devices LC") (part "0805 4.7KΩ (4701) 1%"))
    )
    (comp (ref "R74")
      (value "1KΩ (1001) ±1%")
      (footprint "0805_R")
      (description "贴片电阻")
      (libsource (lib "Miscellaneous Devices LC") (part "0805 1KΩ (1001) 1%"))
    )
    (comp (ref "R75")
      (value "4.7KΩ (4701) ±1%")
      (footprint "0805_R")
      (description "贴片电阻")
      (libsource (lib "Miscellaneous Devices LC") (part "0805 4.7KΩ (4701) 1%"))
    )
    (comp (ref "S1")
      (value "SW-PB")
      (footprint "SW_PB2_A1")
      (description "微动开关")
      (fields (field (name "PUBLISHER") "Altium Limited"))
      (libsource (lib "fszhang") (part "SW-PB"))
    )
    (comp (ref "S2")
      (value "SW-PB")
      (footprint "SW_PB2_A1")
      (description "微动开关")
      (fields (field (name "PUBLISHER") "Altium Limited"))
      (libsource (lib "fszhang") (part "SW-PB"))
    )
    (comp (ref "S3")
      (value "SW-PB")
      (footprint "SW_PB2_A1")
      (description "微动开关")
      (fields (field (name "PUBLISHER") "Altium Limited"))
      (libsource (lib "fszhang") (part "SW-PB"))
    )
    (comp (ref "S4")
      (value "SW-PB")
      (footprint "SW_PB2_A1")
      (description "微动开关")
      (fields (field (name "PUBLISHER") "Altium Limited"))
      (libsource (lib "fszhang") (part "SW-PB"))
    )
    (comp (ref "S5")
      (value "SW-PB")
      (footprint "SW_PB2_A1")
      (description "微动开关")
      (fields (field (name "PUBLISHER") "Altium Limited"))
      (libsource (lib "fszhang") (part "SW-PB"))
    )
    (comp (ref "T1") (value "M3铜柱螺丝孔") (footprint "螺丝孔-3mm") (libsource (lib "fszhang") (part "M3铜柱螺丝孔")))
    (comp (ref "T2") (value "M3铜柱螺丝孔") (footprint "螺丝孔-3mm") (libsource (lib "fszhang") (part "M3铜柱螺丝孔")))
    (comp (ref "T3") (value "M3铜柱螺丝孔") (footprint "螺丝孔-3mm") (libsource (lib "fszhang") (part "M3铜柱螺丝孔")))
    (comp (ref "T4") (value "M3铜柱螺丝孔") (footprint "螺丝孔-3mm") (libsource (lib "fszhang") (part "M3铜柱螺丝孔")))
    (comp (ref "T5") (value "M3铜柱螺丝孔") (footprint "螺丝孔-3mm") (libsource (lib "fszhang") (part "M3铜柱螺丝孔")))
    (comp (ref "T6")
      (value "QS30-1")
      (footprint "QS30-1")
      (description "南昌辉光管")
      (libsource (lib "fszhang") (part "QS30-1"))
    )
    (comp (ref "T7")
      (value "QS30-1")
      (footprint "QS30-1")
      (description "南昌辉光管")
      (libsource (lib "fszhang") (part "QS30-1"))
    )
    (comp (ref "T8")
      (value "QS30-1")
      (footprint "QS30-1")
      (description "南昌辉光管")
      (libsource (lib "fszhang") (part "QS30-1"))
    )
    (comp (ref "T9")
      (value "QS30-1")
      (footprint "QS30-1")
      (description "南昌辉光管")
      (libsource (lib "fszhang") (part "QS30-1"))
    )
    (comp (ref "U1")
      (value "MP1584 Module")
      (footprint "MP1584 Module")
      (libsource (lib "fszhang") (part "MP1584 Module"))
    )
    (comp (ref "U2")
      (value "WS2812-LED")
      (footprint "WS2812")
      (libsource (lib "fszhang") (part "WS2812-LED"))
    )
    (comp (ref "U3")
      (value "WS2812-LED")
      (footprint "WS2812")
      (libsource (lib "fszhang") (part "WS2812-LED"))
    )
    (comp (ref "U4")
      (value "WS2812-LED")
      (footprint "WS2812")
      (libsource (lib "fszhang") (part "WS2812-LED"))
    )
    (comp (ref "U5")
      (value "WS2812-LED")
      (footprint "WS2812")
      (libsource (lib "fszhang") (part "WS2812-LED"))
    )
    (comp (ref "U6")
      (value "MC34063A")
      (footprint "SOIC-8_150mil")
      (libsource (lib "NIXIEClock_SCHLib") (part "MC34063A"))
    )
    (comp (ref "U7")
      (value "STM32F103RBT6")
      (footprint "LQFP-64_10x10x05P")
      (description "ARM")
      (libsource (lib "Miscellaneous Devices LC") (part "STM32F103RBT6"))
    )
    (comp (ref "U8")
      (value "CH340G")
      (footprint "SOIC-16_150mil")
      (description "USB")
      (libsource (lib "Miscellaneous Devices LC") (part "CH340G_[C14267]"))
    )
    (comp (ref "U9")
      (value "74HC595D")
      (footprint "SOIC-16_150mil")
      (description "74系列逻辑芯片")
      (libsource (lib "Miscellaneous Devices LC") (part "74HC595D"))
    )
    (comp (ref "U10")
      (value "74HC595D")
      (footprint "SOIC-16_150mil")
      (description "74系列逻辑芯片")
      (libsource (lib "Miscellaneous Devices LC") (part "74HC595D"))
    )
    (comp (ref "U11")
      (value "74HC595D")
      (footprint "SOIC-16_150mil")
      (description "74系列逻辑芯片")
      (libsource (lib "Miscellaneous Devices LC") (part "74HC595D"))
    )
    (comp (ref "U12")
      (value "74HC595D")
      (footprint "SOIC-16_150mil")
      (description "74系列逻辑芯片")
      (libsource (lib "Miscellaneous Devices LC") (part "74HC595D"))
    )
    (comp (ref "U13")
      (value "74HC595D")
      (footprint "SOIC-16_150mil")
      (description "74系列逻辑芯片")
      (libsource (lib "Miscellaneous Devices LC") (part "74HC595D"))
    )
    (comp (ref "U14")
      (value "DS18B20")
      (footprint "TO-92A")
      (description "温度传感器")
      (libsource (lib "fszhang") (part "DS18B20"))
    )
    (comp (ref "U15")
      (value "DS3231M+TRL")
      (footprint "SOIC-16_300mil")
      (description "实时时钟")
      (libsource (lib "Miscellaneous Devices LC") (part "DS3231M+TRL"))
    )
    (comp (ref "U16")
      (value "HX1838")
      (footprint "HS0038B")
      (description "红外接收器")
      (libsource (lib "fszhang") (part "HS0038B"))
    )
    (comp (ref "UP1")
      (value "Neon")
      (footprint "Neon")
      (description "氖泡")
      (libsource (lib "fszhang") (part "Neon"))
    )
    (comp (ref "UP2")
      (value "Neon")
      (footprint "Neon")
      (description "氖泡")
      (libsource (lib "fszhang") (part "Neon"))
    )
    (comp (ref "VR1")
      (value "AMS1117-3.3")
      (footprint "SOT-223")
      (description "低压差线性稳压(LDO)")
      (libsource (lib "Miscellaneous Devices LC") (part "SOT-223 AMS1117-3.3"))
    )
    (comp (ref "Y1")
      (value "8M")
      (footprint "X-SM49")
      (description "晶振")
      (fields (field (name "ALTIUM_VALUE") "8M") (field (name "PUBLISHER") "Altium Limited"))
      (libsource (lib "fszhang") (part "XTAL"))
    )
    (comp (ref "Y2")
      (value "12M")
      (footprint "X-SM49")
      (description "晶振")
      (fields (field (name "PUBLISHER") "Altium Limited"))
      (libsource (lib "fszhang") (part "XTAL"))
    )
  )
  (nets
    (net (code "1") (name "+5") (class "Default")
      (node (ref "C1") (pin "2") (pinfunction "2_2") (pintype "passive"))
      (node (ref "C19") (pin "1") (pinfunction "1_1") (pintype "passive"))
      (node (ref "C20") (pin "1") (pinfunction "1_1") (pintype "passive"))
      (node (ref "C21") (pin "1") (pinfunction "1_1") (pintype "passive"))
      (node (ref "C22") (pin "1") (pinfunction "1_1") (pintype "passive"))
      (node (ref "C23") (pin "1") (pinfunction "1_1") (pintype "passive"))
      (node (ref "C4") (pin "1") (pinfunction "1_1") (pintype "passive"))
      (node (ref "C5") (pin "1") (pinfunction "1_1") (pintype "passive"))
      (node (ref "C6") (pin "1") (pinfunction "1_1") (pintype "passive"))
      (node (ref "C7") (pin "1") (pinfunction "1_1") (pintype "passive"))
      (node (ref "D1") (pin "1") (pinfunction "A_1") (pintype "passive"))
      (node (ref "J4") (pin "1") (pinfunction "1_1") (pintype "passive"))
      (node (ref "J7") (pin "1") (pinfunction "VCC_1") (pintype "passive"))
      (node (ref "J8") (pin "1") (pinfunction "0_1") (pintype "passive"))
      (node (ref "P2") (pin "4") (pinfunction "4_4") (pintype "passive"))
      (node (ref "U1") (pin "3") (pinfunction "OUT+_3") (pintype "passive"))
      (node (ref "U10") (pin "10") (pinfunction "~{SRCLR}_10") (pintype "input"))
      (node (ref "U10") (pin "16") (pinfunction "VCC_16") (pintype "power_in"))
      (node (ref "U11") (pin "10") (pinfunction "~{SRCLR}_10") (pintype "input"))
      (node (ref "U11") (pin "16") (pinfunction "VCC_16") (pintype "power_in"))
      (node (ref "U12") (pin "10") (pinfunction "~{SRCLR}_10") (pintype "input"))
      (node (ref "U12") (pin "16") (pinfunction "VCC_16") (pintype "power_in"))
      (node (ref "U13") (pin "10") (pinfunction "~{SRCLR}_10") (pintype "input"))
      (node (ref "U13") (pin "16") (pinfunction "VCC_16") (pintype "power_in"))
      (node (ref "U2") (pin "1") (pinfunction "VDD_1") (pintype "passive"))
      (node (ref "U3") (pin "1") (pinfunction "VDD_1") (pintype "passive"))
      (node (ref "U4") (pin "1") (pinfunction "VDD_1") (pintype "passive"))
      (node (ref "U5") (pin "1") (pinfunction "VDD_1") (pintype "passive"))
      (node (ref "U9") (pin "10") (pinfunction "~{SRCLR}_10") (pintype "input"))
      (node (ref "U9") (pin "16") (pinfunction "VCC_16") (pintype "power_in"))
      (node (ref "VR1") (pin "3") (pinfunction "Vin_3") (pintype "passive"))
    )
    (net (code "2") (name "+12") (class "Default")
      (node (ref "C11") (pin "2") (pinfunction "2_2") (pintype "passive"))
      (node (ref "C12") (pin "1") (pinfunction "1_1") (pintype "passive"))
      (node (ref "J1") (pin "1") (pinfunction "1_1") (pintype "power_in"))
      (node (ref "J3") (pin "1") (pinfunction "1_1") (pintype "passive"))
      (node (ref "L1") (pin "1") (pinfunction "1_1") (pintype "passive"))
      (node (ref "U1") (pin "2") (pinfunction "IN+_2") (pintype "passive"))
      (node (ref "U6") (pin "1") (pinfunction "SC_1") (pintype "passive"))
      (node (ref "U6") (pin "6") (pinfunction "VCC_6") (pintype "passive"))
      (node (ref "U6") (pin "7") (pinfunction "IPK_7") (pintype "passive"))
      (node (ref "U6") (pin "8") (pinfunction "DRI_8") (pintype "passive"))
    )
    (net (code "3") (name "/BEEP") (class "Default")
      (node (ref "R74") (pin "1") (pinfunction "1_1") (pintype "passive"))
      (node (ref "U7") (pin "58") (pinfunction "PB6_58") (pintype "bidirectional"))
    )
    (net (code "4") (name "/BT0") (class "Default")
      (node (ref "R17") (pin "2") (pinfunction "2_2") (pintype "passive"))
      (node (ref "R60") (pin "1") (pinfunction "1_1") (pintype "passive"))
      (node (ref "U7") (pin "60") (pinfunction "BOOT0_60") (pintype "input"))
    )
    (net (code "5") (name "/BT1") (class "Default")
      (node (ref "R14") (pin "2") (pinfunction "2_2") (pintype "passive"))
      (node (ref "U7") (pin "28") (pinfunction "PB2_28") (pintype "bidirectional"))
    )
    (net (code "6") (name "/DIN") (class "Default")
      (node (ref "R39") (pin "2") (pinfunction "2_2") (pintype "passive"))
      (node (ref "U7") (pin "14") (pinfunction "PA0-WKUP_14") (pintype "bidirectional"))
      (node (ref "U9") (pin "14") (pinfunction "SER_14") (pintype "input"))
    )
    (net (code "7") (name "/DS18B20") (class "Default")
      (node (ref "R66") (pin "1") (pinfunction "1_1") (pintype "passive"))
      (node (ref "U14") (pin "2") (pinfunction "DQ_2") (pintype "passive"))
      (node (ref "U7") (pin "61") (pinfunction "PB8_61") (pintype "bidirectional"))
    )
    (net (code "8") (name "/Dot1") (class "Default")
      (node (ref "R2") (pin "2") (pinfunction "2_2") (pintype "passive"))
      (node (ref "U7") (pin "29") (pinfunction "PB10_29") (pintype "bidirectional"))
    )
    (net (code "9") (name "/Dot2") (class "Default")
      (node (ref "R9") (pin "2") (pinfunction "2_2") (pintype "passive"))
      (node (ref "U7") (pin "30") (pinfunction "PB11_30") (pintype "bidirectional"))
    )
    (net (code "10") (name "/HX1838") (class "Default")
      (node (ref "R75") (pin "2") (pinfunction "2_2") (pintype "passive"))
      (node (ref "U16") (pin "1") (pinfunction "OUT_1") (pintype "passive"))
      (node (ref "U7") (pin "59") (pinfunction "PB7_59") (pintype "bidirectional"))
    )
    (net (code "11") (name "/INT#{slash}SQW") (class "Default")
      (node (ref "R73") (pin "2") (pinfunction "2_2") (pintype "passive"))
      (node (ref "U15") (pin "3") (pinfunction "~{INT}/SQW_3") (pintype "passive"))
      (node (ref "U7") (pin "54") (pinfunction "PD2_54") (pintype "bidirectional"))
    )
    (net (code "12") (name "/KEY1") (class "Default")
      (node (ref "C28") (pin "2") (pinfunction "2_2") (pintype "passive"))
      (node (ref "R69") (pin "2") (pinfunction "2_2") (pintype "passive"))
      (node (ref "S2") (pin "2") (pinfunction "2_2") (pintype "passive"))
      (node (ref "U7") (pin "51") (pinfunction "PC10_51") (pintype "bidirectional"))
    )
    (net (code "13") (name "/KEY2") (class "Default")
      (node (ref "C29") (pin "2") (pinfunction "2_2") (pintype "passive"))
      (node (ref "R70") (pin "2") (pinfunction "2_2") (pintype "passive"))
      (node (ref "S3") (pin "2") (pinfunction "2_2") (pintype "passive"))
      (node (ref "U7") (pin "52") (pinfunction "PC11_52") (pintype "bidirectional"))
    )
    (net (code "14") (name "/KEY3") (class "Default")
      (node (ref "C30") (pin "2") (pinfunction "2_2") (pintype "passive"))
      (node (ref "R71") (pin "2") (pinfunction "2_2") (pintype "passive"))
      (node (ref "S4") (pin "2") (pinfunction "2_2") (pintype "passive"))
      (node (ref "U7") (pin "53") (pinfunction "PC12_53") (pintype "bidirectional"))
    )
    (net (code "15") (name "/KEY4") (class "Default")
      (node (ref "C31") (pin "2") (pinfunction "2_2") (pintype "passive"))
      (node (ref "R72") (pin "2") (pinfunction "2_2") (pintype "passive"))
      (node (ref "S5") (pin "2") (pinfunction "2_2") (pintype "passive"))
      (node (ref "U7") (pin "50") (pinfunction "PA15_50") (pintype "bidirectional"))
    )
    (net (code "16") (name "/LED_DEBUG") (class "Default")
      (node (ref "R13") (pin "2") (pinfunction "2_2") (pintype "passive"))
      (node (ref "U7") (pin "22") (pinfunction "PA6_22") (pintype "bidirectional"))
    )
    (net (code "17") (name "/Lamp") (class "Default")
      (node (ref "P1") (pin "1") (pinfunction "1_1") (pintype "passive"))
      (node (ref "U7") (pin "23") (pinfunction "PA7_23") (pintype "bidirectional"))
    )
    (net (code "18") (name "/LatchCLK") (class "Default")
      (node (ref "R21") (pin "2") (pinfunction "2_2") (pintype "passive"))
      (node (ref "U10") (pin "12") (pinfunction "RCLK_12") (pintype "input"))
      (node (ref "U11") (pin "12") (pinfunction "RCLK_12") (pintype "input"))
      (node (ref "U12") (pin "12") (pinfunction "RCLK_12") (pintype "input"))
      (node (ref "U13") (pin "12") (pinfunction "RCLK_12") (pintype "input"))
      (node (ref "U7") (pin "16") (pinfunction "PA2_16") (pintype "bidirectional"))
      (node (ref "U9") (pin "12") (pinfunction "RCLK_12") (pintype "input"))
    )
    (net (code "19") (name "/MetalKey") (class "Default")
      (node (ref "C3") (pin "2") (pinfunction "2_2") (pintype "passive"))
      (node (ref "P1") (pin "4") (pinfunction "4_4") (pintype "passive"))
      (node (ref "R1") (pin "2") (pinfunction "2_2") (pintype "passive"))
      (node (ref "U7") (pin "45") (pinfunction "PA12_45") (pintype "bidirectional"))
    )
    (net (code "20") (name "/OE#") (class "Default")
      (node (ref "U10") (pin "13") (pinfunction "~{OE}_13") (pintype "input"))
      (node (ref "U11") (pin "13") (pinfunction "~{OE}_13") (pintype "input"))
      (node (ref "U12") (pin "13") (pinfunction "~{OE}_13") (pintype "input"))
      (node (ref "U13") (pin "13") (pinfunction "~{OE}_13") (pintype "input"))
      (node (ref "U7") (pin "17") (pinfunction "PA3_17") (pintype "bidirectional"))
      (node (ref "U9") (pin "13") (pinfunction "~{OE}_13") (pintype "input"))
    )
    (net (code "21") (name "/RGB") (class "Default")
      (node (ref "R12") (pin "1") (pinfunction "1_1") (pintype "passive"))
      (node (ref "U2") (pin "4") (pinfunction "DI_4") (pintype "passive"))
      (node (ref "U7") (pin "26") (pinfunction "PB0_26") (pintype "bidirectional"))
    )
    (net (code "22") (name "/RST") (class "Default")
      (node (ref "C18") (pin "2") (pinfunction "2_2") (pintype "passive"))
      (node (ref "D4") (pin "1") (pinfunction "A_1") (pintype "passive"))
      (node (ref "R18") (pin "2") (pinfunction "2_2") (pintype "passive"))
      (node (ref "S1") (pin "1") (pinfunction "1_1") (pintype "passive"))
      (node (ref "U7") (pin "7") (pinfunction "NRST_7") (pintype "bidirectional"))
    )
    (net (code "23") (name "/RX1") (class "Default")
      (node (ref "P3") (pin "2") (pinfunction "2_2") (pintype "passive"))
      (node (ref "U7") (pin "43") (pinfunction "PA10_43") (pintype "bidirectional"))
      (node (ref "U8") (pin "2") (pinfunction "TXD_2") (pintype "passive"))
    )
    (net (code "24") (name "/SCL") (class "Default")
      (node (ref "R67") (pin "1") (pinfunction "1_1") (pintype "passive"))
      (node (ref "U15") (pin "16") (pinfunction "SCL_16") (pintype "passive"))
      (node (ref "U7") (pin "55") (pinfunction "PB3_55") (pintype "bidirectional"))
    )
    (net (code "25") (name "/SDA") (class "Default")
      (node (ref "R68") (pin "1") (pinfunction "1_1") (pintype "passive"))
      (node (ref "U15") (pin "15") (pinfunction "SDA_15") (pintype "passive"))
      (node (ref "U7") (pin "56") (pinfunction "PB4_56") (pintype "bidirectional"))
    )
    (net (code "26") (name "/SWCLK") (class "Default")
      (node (ref "P2") (pin "2") (pinfunction "2_2") (pintype "passive"))
      (node (ref "U7") (pin "49") (pinfunction "PA14_49") (pintype "bidirectional"))
    )
    (net (code "27") (name "/SWDIO") (class "Default")
      (node (ref "P2") (pin "3") (pinfunction "3_3") (pintype "passive"))
      (node (ref "U7") (pin "46") (pinfunction "PA13_46") (pintype "bidirectional"))
    )
    (net (code "28") (name "/ShiftCLK") (class "Default")
      (node (ref "R27") (pin "2") (pinfunction "2_2") (pintype "passive"))
      (node (ref "U10") (pin "11") (pinfunction "SRCLK_11") (pintype "input"))
      (node (ref "U11") (pin "11") (pinfunction "SRCLK_11") (pintype "input"))
      (node (ref "U12") (pin "11") (pinfunction "SRCLK_11") (pintype "input"))
      (node (ref "U13") (pin "11") (pinfunction "SRCLK_11") (pintype "input"))
      (node (ref "U7") (pin "15") (pinfunction "PA1_15") (pintype "bidirectional"))
      (node (ref "U9") (pin "11") (pinfunction "SRCLK_11") (pintype "input"))
    )
    (net (code "29") (name "/TX1") (class "Default")
      (node (ref "P3") (pin "3") (pinfunction "3_3") (pintype "passive"))
      (node (ref "U7") (pin "42") (pinfunction "PA9_42") (pintype "bidirectional"))
      (node (ref "U8") (pin "3") (pinfunction "RXD_3") (pintype "passive"))
    )
    (net (code "30") (name "/Tube1-0") (class "Default")
      (node (ref "Q4") (pin "1") (pinfunction "B_1") (pintype "passive"))
      (node (ref "R22") (pin "2") (pinfunction "2_2") (pintype "passive"))
    )
    (net (code "31") (name "/Tube1-1") (class "Default")
      (node (ref "Q13") (pin "1") (pinfunction "B_1") (pintype "passive"))
      (node (ref "R29") (pin "2") (pinfunction "2_2") (pintype "passive"))
    )
    (net (code "32") (name "/Tube1-2") (class "Default")
      (node (ref "Q12") (pin "1") (pinfunction "B_1") (pintype "passive"))
      (node (ref "R34") (pin "2") (pinfunction "2_2") (pintype "passive"))
    )
    (net (code "33") (name "/Tube1-3") (class "Default")
      (node (ref "Q11") (pin "1") (pinfunction "B_1") (pintype "passive"))
      (node (ref "R40") (pin "2") (pinfunction "2_2") (pintype "passive"))
    )
    (net (code "34") (name "/Tube1-4") (class "Default")
      (node (ref "Q10") (pin "1") (pinfunction "B_1") (pintype "passive"))
      (node (ref "R45") (pin "2") (pinfunction "2_2") (pintype "passive"))
    )
    (net (code "35") (name "/Tube1-5") (class "Default")
      (node (ref "Q9") (pin "1") (pinfunction "B_1") (pintype "passive"))
      (node (ref "R50") (pin "2") (pinfunction "2_2") (pintype "passive"))
    )
    (net (code "36") (name "/Tube1-6") (class "Default")
      (node (ref "Q8") (pin "1") (pinfunction "B_1") (pintype "passive"))
      (node (ref "R55") (pin "2") (pinfunction "2_2") (pintype "passive"))
    )
    (net (code "37") (name "/Tube1-7") (class "Default")
      (node (ref "Q7") (pin "1") (pinfunction "B_1") (pintype "passive"))
      (node (ref "R61") (pin "2") (pinfunction "2_2") (pintype "passive"))
    )
    (net (code "38") (name "/Tube1-8") (class "Default")
      (node (ref "Q6") (pin "1") (pinfunction "B_1") (pintype "passive"))
      (node (ref "R23") (pin "2") (pinfunction "2_2") (pintype "passive"))
    )
    (net (code "39") (name "/Tube1-9") (class "Default")
      (node (ref "Q5") (pin "1") (pinfunction "B_1") (pintype "passive"))
      (node (ref "R30") (pin "2") (pinfunction "2_2") (pintype "passive"))
    )
    (net (code "40") (name "/Tube2-0") (class "Default")
      (node (ref "Q14") (pin "1") (pinfunction "B_1") (pintype "passive"))
      (node (ref "R35") (pin "2") (pinfunction "2_2") (pintype "passive"))
    )
    (net (code "41") (name "/Tube2-1") (class "Default")
      (node (ref "Q23") (pin "1") (pinfunction "B_1") (pintype "passive"))
      (node (ref "R41") (pin "2") (pinfunction "2_2") (pintype "passive"))
    )
    (net (code "42") (name "/Tube2-2") (class "Default")
      (node (ref "Q22") (pin "1") (pinfunction "B_1") (pintype "passive"))
      (node (ref "R46") (pin "2") (pinfunction "2_2") (pintype "passive"))
    )
    (net (code "43") (name "/Tube2-3") (class "Default")
      (node (ref "Q21") (pin "1") (pinfunction "B_1") (pintype "passive"))
      (node (ref "R51") (pin "2") (pinfunction "2_2") (pintype "passive"))
    )
    (net (code "44") (name "/Tube2-4") (class "Default")
      (node (ref "Q20") (pin "1") (pinfunction "B_1") (pintype "passive"))
      (node (ref "R56") (pin "2") (pinfunction "2_2") (pintype "passive"))
    )
    (net (code "45") (name "/Tube2-5") (class "Default")
      (node (ref "Q19") (pin "1") (pinfunction "B_1") (pintype "passive"))
      (node (ref "R62") (pin "2") (pinfunction "2_2") (pintype "passive"))
    )
    (net (code "46") (name "/Tube2-6") (class "Default")
      (node (ref "Q18") (pin "1") (pinfunction "B_1") (pintype "passive"))
      (node (ref "R24") (pin "2") (pinfunction "2_2") (pintype "passive"))
    )
    (net (code "47") (name "/Tube2-7") (class "Default")
      (node (ref "Q17") (pin "1") (pinfunction "B_1") (pintype "passive"))
      (node (ref "R31") (pin "2") (pinfunction "2_2") (pintype "passive"))
    )
    (net (code "48") (name "/Tube2-8") (class "Default")
      (node (ref "Q16") (pin "1") (pinfunction "B_1") (pintype "passive"))
      (node (ref "R36") (pin "2") (pinfunction "2_2") (pintype "passive"))
    )
    (net (code "49") (name "/Tube2-9") (class "Default")
      (node (ref "Q15") (pin "1") (pinfunction "B_1") (pintype "passive"))
      (node (ref "R42") (pin "2") (pinfunction "2_2") (pintype "passive"))
    )
    (net (code "50") (name "/Tube3-0") (class "Default")
      (node (ref "Q24") (pin "1") (pinfunction "B_1") (pintype "passive"))
      (node (ref "R47") (pin "2") (pinfunction "2_2") (pintype "passive"))
    )
    (net (code "51") (name "/Tube3-1") (class "Default")
      (node (ref "Q33") (pin "1") (pinfunction "B_1") (pintype "passive"))
      (node (ref "R52") (pin "2") (pinfunction "2_2") (pintype "passive"))
    )
    (net (code "52") (name "/Tube3-2") (class "Default")
      (node (ref "Q32") (pin "1") (pinfunction "B_1") (pintype "passive"))
      (node (ref "R57") (pin "2") (pinfunction "2_2") (pintype "passive"))
    )
    (net (code "53") (name "/Tube3-3") (class "Default")
      (node (ref "Q31") (pin "1") (pinfunction "B_1") (pintype "passive"))
      (node (ref "R63") (pin "2") (pinfunction "2_2") (pintype "passive"))
    )
    (net (code "54") (name "/Tube3-4") (class "Default")
      (node (ref "Q30") (pin "1") (pinfunction "B_1") (pintype "passive"))
      (node (ref "R25") (pin "2") (pinfunction "2_2") (pintype "passive"))
    )
    (net (code "55") (name "/Tube3-5") (class "Default")
      (node (ref "Q29") (pin "1") (pinfunction "B_1") (pintype "passive"))
      (node (ref "R32") (pin "2") (pinfunction "2_2") (pintype "passive"))
    )
    (net (code "56") (name "/Tube3-6") (class "Default")
      (node (ref "Q28") (pin "1") (pinfunction "B_1") (pintype "passive"))
      (node (ref "R37") (pin "2") (pinfunction "2_2") (pintype "passive"))
    )
    (net (code "57") (name "/Tube3-7") (class "Default")
      (node (ref "Q27") (pin "1") (pinfunction "B_1") (pintype "passive"))
      (node (ref "R43") (pin "2") (pinfunction "2_2") (pintype "passive"))
    )
    (net (code "58") (name "/Tube3-8") (class "Default")
      (node (ref "Q26") (pin "1") (pinfunction "B_1") (pintype "passive"))
      (node (ref "R48") (pin "2") (pinfunction "2_2") (pintype "passive"))
    )
    (net (code "59") (name "/Tube3-9") (class "Default")
      (node (ref "Q25") (pin "1") (pinfunction "B_1") (pintype "passive"))
      (node (ref "R53") (pin "2") (pinfunction "2_2") (pintype "passive"))
    )
    (net (code "60") (name "/Tube4-0") (class "Default")
      (node (ref "Q34") (pin "1") (pinfunction "B_1") (pintype "passive"))
      (node (ref "R58") (pin "2") (pinfunction "2_2") (pintype "passive"))
    )
    (net (code "61") (name "/Tube4-1") (class "Default")
      (node (ref "Q43") (pin "1") (pinfunction "B_1") (pintype "passive"))
      (node (ref "R64") (pin "2") (pinfunction "2_2") (pintype "passive"))
    )
    (net (code "62") (name "/Tube4-2") (class "Default")
      (node (ref "Q42") (pin "1") (pinfunction "B_1") (pintype "passive"))
      (node (ref "R26") (pin "2") (pinfunction "2_2") (pintype "passive"))
    )
    (net (code "63") (name "/Tube4-3") (class "Default")
      (node (ref "Q41") (pin "1") (pinfunction "B_1") (pintype "passive"))
      (node (ref "R33") (pin "2") (pinfunction "2_2") (pintype "passive"))
    )
    (net (code "64") (name "/Tube4-4") (class "Default")
      (node (ref "Q40") (pin "1") (pinfunction "B_1") (pintype "passive"))
      (node (ref "R38") (pin "2") (pinfunction "2_2") (pintype "passive"))
    )
    (net (code "65") (name "/Tube4-5") (class "Default")
      (node (ref "Q39") (pin "1") (pinfunction "B_1") (pintype "passive"))
      (node (ref "R44") (pin "2") (pinfunction "2_2") (pintype "passive"))
    )
    (net (code "66") (name "/Tube4-6") (class "Default")
      (node (ref "Q38") (pin "1") (pinfunction "B_1") (pintype "passive"))
      (node (ref "R49") (pin "2") (pinfunction "2_2") (pintype "passive"))
    )
    (net (code "67") (name "/Tube4-7") (class "Default")
      (node (ref "Q37") (pin "1") (pinfunction "B_1") (pintype "passive"))
      (node (ref "R54") (pin "2") (pinfunction "2_2") (pintype "passive"))
    )
    (net (code "68") (name "/Tube4-8") (class "Default")
      (node (ref "Q36") (pin "1") (pinfunction "B_1") (pintype "passive"))
      (node (ref "R59") (pin "2") (pinfunction "2_2") (pintype "passive"))
    )
    (net (code "69") (name "/Tube4-9") (class "Default")
      (node (ref "Q35") (pin "1") (pinfunction "B_1") (pintype "passive"))
      (node (ref "R65") (pin "2") (pinfunction "2_2") (pintype "passive"))
    )
    (net (code "70") (name "/UD+") (class "Default")
      (node (ref "J7") (pin "3") (pinfunction "D+_3") (pintype "passive"))
      (node (ref "U8") (pin "5") (pinfunction "UD+_5") (pintype "passive"))
    )
    (net (code "71") (name "/UD-") (class "Default")
      (node (ref "J7") (pin "2") (pinfunction "D-_2") (pintype "passive"))
      (node (ref "U8") (pin "6") (pinfunction "UD-_6") (pintype "passive"))
    )
    (net (code "72") (name "3V3") (class "Default")
      (node (ref "C15") (pin "1") (pinfunction "1_1") (pintype "passive"))
      (node (ref "C16") (pin "1") (pinfunction "1_1") (pintype "passive"))
      (node (ref "C17") (pin "1") (pinfunction "1_1") (pintype "passive"))
      (node (ref "C2") (pin "2") (pinfunction "2_2") (pintype "passive"))
      (node (ref "C27") (pin "2") (pinfunction "2_2") (pintype "passive"))
      (node (ref "C32") (pin "1") (pinfunction "1_1") (pintype "passive"))
      (node (ref "D3") (pin "A") (pinfunction "A_A") (pintype "passive"))
      (node (ref "J5") (pin "1") (pinfunction "1_1") (pintype "passive"))
      (node (ref "P1") (pin "2") (pinfunction "2_2") (pintype "passive"))
      (node (ref "Q45") (pin "2") (pinfunction "E_2") (pintype "passive"))
      (node (ref "R1") (pin "1") (pinfunction "1_1") (pintype "passive"))
      (node (ref "R12") (pin "2") (pinfunction "2_2") (pintype "passive"))
      (node (ref "R18") (pin "1") (pinfunction "1_1") (pintype "passive"))
      (node (ref "R19") (pin "2") (pinfunction "2_2") (pintype "passive"))
      (node (ref "R21") (pin "1") (pinfunction "1_1") (pintype "passive"))
      (node (ref "R27") (pin "1") (pinfunction "1_1") (pintype "passive"))
      (node (ref "R39") (pin "1") (pinfunction "1_1") (pintype "passive"))
      (node (ref "R66") (pin "2") (pinfunction "2_2") (pintype "passive"))
      (node (ref "R67") (pin "2") (pinfunction "2_2") (pintype "passive"))
      (node (ref "R68") (pin "2") (pinfunction "2_2") (pintype "passive"))
      (node (ref "R69") (pin "1") (pinfunction "1_1") (pintype "passive"))
      (node (ref "R70") (pin "1") (pinfunction "1_1") (pintype "passive"))
      (node (ref "R71") (pin "1") (pinfunction "1_1") (pintype "passive"))
      (node (ref "R72") (pin "1") (pinfunction "1_1") (pintype "passive"))
      (node (ref "R73") (pin "1") (pinfunction "1_1") (pintype "passive"))
      (node (ref "R75") (pin "1") (pinfunction "1_1") (pintype "passive"))
      (node (ref "U14") (pin "3") (pinfunction "VDD_3") (pintype "passive"))
      (node (ref "U15") (pin "2") (pinfunction "VCC_2") (pintype "passive"))
      (node (ref "U16") (pin "3") (pinfunction "VCC_3") (pintype "passive"))
      (node (ref "U7") (pin "1") (pinfunction "VBAT_1") (pintype "power_in"))
      (node (ref "U7") (pin "13") (pinfunction "VDDA_13") (pintype "power_in"))
      (node (ref "U7") (pin "19") (pinfunction "VDD_4_19") (pintype "power_in"))
      (node (ref "U7") (pin "32") (pinfunction "VDD_1_32") (pintype "power_in"))
      (node (ref "U7") (pin "48") (pinfunction "VDD_2_48") (pintype "power_in"))
      (node (ref "U7") (pin "64") (pinfunction "VDD_3_64") (pintype "power_in"))
      (node (ref "U8") (pin "16") (pinfunction "VCC_16") (pintype "passive"))
      (node (ref "VR1") (pin "2") (pinfunction "Vout_2") (pintype "passive"))
    )
    (net (code "73") (name "DGND") (class "Default")
      (node (ref "BT1") (pin "2") (pinfunction "-_2") (pintype "passive"))
      (node (ref "C13") (pin "1") (pinfunction "1_1") (pintype "passive"))
      (node (ref "C14") (pin "1") (pinfunction "1_1") (pintype "passive"))
      (node (ref "C15") (pin "2") (pinfunction "2_2") (pintype "passive"))
      (node (ref "C16") (pin "2") (pinfunction "2_2") (pintype "passive"))
      (node (ref "C17") (pin "2") (pinfunction "2_2") (pintype "passive"))
      (node (ref "C18") (pin "1") (pinfunction "1_1") (pintype "passive"))
      (node (ref "C19") (pin "2") (pinfunction "2_2") (pintype "passive"))
      (node (ref "C20") (pin "2") (pinfunction "2_2") (pintype "passive"))
      (node (ref "C21") (pin "2") (pinfunction "2_2") (pintype "passive"))
      (node (ref "C22") (pin "2") (pinfunction "2_2") (pintype "passive"))
      (node (ref "C23") (pin "2") (pinfunction "2_2") (pintype "passive"))
      (node (ref "C24") (pin "2") (pinfunction "2_2") (pintype "passive"))
      (node (ref "C25") (pin "2") (pinfunction "2_2") (pintype "passive"))
      (node (ref "C26") (pin "2") (pinfunction "2_2") (pintype "passive"))
      (node (ref "C27") (pin "1") (pinfunction "1_1") (pintype "passive"))
      (node (ref "C28") (pin "1") (pinfunction "1_1") (pintype "passive"))
      (node (ref "C29") (pin "1") (pinfunction "1_1") (pintype "passive"))
      (node (ref "C3") (pin "1") (pinfunction "1_1") (pintype "passive"))
      (node (ref "C30") (pin "1") (pinfunction "1_1") (pintype "passive"))
      (node (ref "C31") (pin "1") (pinfunction "1_1") (pintype "passive"))
      (node (ref "C32") (pin "2") (pinfunction "2_2") (pintype "passive"))
      (node (ref "J7") (pin "4") (pinfunction "ID_4") (pintype "passive"))
      (node (ref "J7") (pin "5") (pinfunction "VSS_5") (pintype "passive"))
      (node (ref "L2") (pin "2") (pinfunction "2_2") (pintype "passive"))
      (node (ref "P1") (pin "3") (pinfunction "3_3") (pintype "passive"))
      (node (ref "P2") (pin "1") (pinfunction "1_1") (pintype "passive"))
      (node (ref "P3") (pin "1") (pinfunction "1_1") (pintype "passive"))
      (node (ref "Q46") (pin "2") (pinfunction "E_2") (pintype "passive"))
      (node (ref "R14") (pin "1") (pinfunction "1_1") (pintype "passive"))
      (node (ref "R17") (pin "1") (pinfunction "1_1") (pintype "passive"))
      (node (ref "S1") (pin "2") (pinfunction "2_2") (pintype "passive"))
      (node (ref "S2") (pin "1") (pinfunction "1_1") (pintype "passive"))
      (node (ref "S3") (pin "1") (pinfunction "1_1") (pintype "passive"))
      (node (ref "S4") (pin "1") (pinfunction "1_1") (pintype "passive"))
      (node (ref "S5") (pin "1") (pinfunction "1_1") (pintype "passive"))
      (node (ref "T2") (pin "1") (pinfunction "1_1") (pintype "passive"))
      (node (ref "T3") (pin "1") (pinfunction "1_1") (pintype "passive"))
      (node (ref "T4") (pin "1") (pinfunction "1_1") (pintype "passive"))
      (node (ref "T5") (pin "1") (pinfunction "1_1") (pintype "passive"))
      (node (ref "U10") (pin "8") (pinfunction "GND_8") (pintype "power_in"))
      (node (ref "U11") (pin "8") (pinfunction "GND_8") (pintype "power_in"))
      (node (ref "U12") (pin "8") (pinfunction "GND_8") (pintype "power_in"))
      (node (ref "U13") (pin "8") (pinfunction "GND_8") (pintype "power_in"))
      (node (ref "U14") (pin "1") (pinfunction "GND_1") (pintype "passive"))
      (node (ref "U15") (pin "10") (pinfunction "N.C._10") (pintype "passive"))
      (node (ref "U15") (pin "11") (pinfunction "N.C._11") (pintype "passive"))
      (node (ref "U15") (pin "12") (pinfunction "N.C._12") (pintype "passive"))
      (node (ref "U15") (pin "13") (pinfunction "GND_13") (pintype "passive"))
      (node (ref "U15") (pin "5") (pinfunction "N.C._5") (pintype "passive"))
      (node (ref "U15") (pin "6") (pinfunction "N.C._6") (pintype "passive"))
      (node (ref "U15") (pin "7") (pinfunction "N.C._7") (pintype "passive"))
      (node (ref "U15") (pin "8") (pinfunction "N.C._8") (pintype "passive"))
      (node (ref "U15") (pin "9") (pinfunction "N.C._9") (pintype "passive"))
      (node (ref "U16") (pin "2") (pinfunction "GND_2") (pintype "passive"))
      (node (ref "U7") (pin "12") (pinfunction "VSSA_12") (pintype "power_in"))
      (node (ref "U7") (pin "18") (pinfunction "VSS_4_18") (pintype "power_in"))
      (node (ref "U7") (pin "31") (pinfunction "VSS_1_31") (pintype "power_in"))
      (node (ref "U7") (pin "47") (pinfunction "VSS_2_47") (pintype "power_in"))
      (node (ref "U7") (pin "63") (pinfunction "VSS_3_63") (pintype "power_in"))
      (node (ref "U8") (pin "1") (pinfunction "GND_1") (pintype "passive"))
      (node (ref "U9") (pin "8") (pinfunction "GND_8") (pintype "power_in"))
    )
    (net (code "74") (name "GND") (class "Default")
      (node (ref "C1") (pin "1") (pinfunction "1_1") (pintype "passive"))
      (node (ref "C10") (pin "2") (pinfunction "2_2") (pintype "passive"))
      (node (ref "C11") (pin "1") (pinfunction "1_1") (pintype "passive"))
      (node (ref "C12") (pin "2") (pinfunction "2_2") (pintype "passive"))
      (node (ref "C2") (pin "1") (pinfunction "1_1") (pintype "passive"))
      (node (ref "C4") (pin "2") (pinfunction "2_2") (pintype "passive"))
      (node (ref "C5") (pin "2") (pinfunction "2_2") (pintype "passive"))
      (node (ref "C6") (pin "2") (pinfunction "2_2") (pintype "passive"))
      (node (ref "C7") (pin "2") (pinfunction "2_2") (pintype "passive"))
      (node (ref "C8") (pin "1") (pinfunction "1_1") (pintype "passive"))
      (node (ref "C9") (pin "2") (pinfunction "2_2") (pintype "passive"))
      (node (ref "D1") (pin "2") (pinfunction "K_2") (pintype "passive"))
      (node (ref "J1") (pin "2") (pinfunction "2_2") (pintype "power_in"))
      (node (ref "J1") (pin "3") (pinfunction "3_3") (pintype "power_in"))
      (node (ref "J6") (pin "1") (pinfunction "1_1") (pintype "passive"))
      (node (ref "L2") (pin "1") (pinfunction "1_1") (pintype "passive"))
      (node (ref "Q1") (pin "2") (pinfunction "E_2") (pintype "passive"))
      (node (ref "Q10") (pin "2") (pinfunction "E_2") (pintype "passive"))
      (node (ref "Q11") (pin "2") (pinfunction "E_2") (pintype "passive"))
      (node (ref "Q12") (pin "2") (pinfunction "E_2") (pintype "passive"))
      (node (ref "Q13") (pin "2") (pinfunction "E_2") (pintype "passive"))
      (node (ref "Q14") (pin "2") (pinfunction "E_2") (pintype "passive"))
      (node (ref "Q15") (pin "2") (pinfunction "E_2") (pintype "passive"))
      (node (ref "Q16") (pin "2") (pinfunction "E_2") (pintype "passive"))
      (node (ref "Q17") (pin "2") (pinfunction "E_2") (pintype "passive"))
      (node (ref "Q18") (pin "2") (pinfunction "E_2") (pintype "passive"))
      (node (ref "Q19") (pin "2") (pinfunction "E_2") (pintype "passive"))
      (node (ref "Q2") (pin "2") (pinfunction "E_2") (pintype "passive"))
      (node (ref "Q20") (pin "2") (pinfunction "E_2") (pintype "passive"))
      (node (ref "Q21") (pin "2") (pinfunction "E_2") (pintype "passive"))
      (node (ref "Q22") (pin "2") (pinfunction "E_2") (pintype "passive"))
      (node (ref "Q23") (pin "2") (pinfunction "E_2") (pintype "passive"))
      (node (ref "Q24") (pin "2") (pinfunction "E_2") (pintype "passive"))
      (node (ref "Q25") (pin "2") (pinfunction "E_2") (pintype "passive"))
      (node (ref "Q26") (pin "2") (pinfunction "E_2") (pintype "passive"))
      (node (ref "Q27") (pin "2") (pinfunction "E_2") (pintype "passive"))
      (node (ref "Q28") (pin "2") (pinfunction "E_2") (pintype "passive"))
      (node (ref "Q29") (pin "2") (pinfunction "E_2") (pintype "passive"))
      (node (ref "Q3") (pin "3") (pinfunction "S_3") (pintype "passive"))
      (node (ref "Q30") (pin "2") (pinfunction "E_2") (pintype "passive"))
      (node (ref "Q31") (pin "2") (pinfunction "E_2") (pintype "passive"))
      (node (ref "Q32") (pin "2") (pinfunction "E_2") (pintype "passive"))
      (node (ref "Q33") (pin "2") (pinfunction "E_2") (pintype "passive"))
      (node (ref "Q34") (pin "2") (pinfunction "E_2") (pintype "passive"))
      (node (ref "Q35") (pin "2") (pinfunction "E_2") (pintype "passive"))
      (node (ref "Q36") (pin "2") (pinfunction "E_2") (pintype "passive"))
      (node (ref "Q37") (pin "2") (pinfunction "E_2") (pintype "passive"))
      (node (ref "Q38") (pin "2") (pinfunction "E_2") (pintype "passive"))
      (node (ref "Q39") (pin "2") (pinfunction "E_2") (pintype "passive"))
      (node (ref "Q4") (pin "2") (pinfunction "E_2") (pintype "passive"))
      (node (ref "Q40") (pin "2") (pinfunction "E_2") (pintype "passive"))
      (node (ref "Q41") (pin "2") (pinfunction "E_2") (pintype "passive"))
      (node (ref "Q42") (pin "2") (pinfunction "E_2") (pintype "passive"))
      (node (ref "Q43") (pin "2") (pinfunction "E_2") (pintype "passive"))
      (node (ref "Q5") (pin "2") (pinfunction "E_2") (pintype "passive"))
      (node (ref "Q6") (pin "2") (pinfunction "E_2") (pintype "passive"))
      (node (ref "Q7") (pin "2") (pinfunction "E_2") (pintype "passive"))
      (node (ref "Q8") (pin "2") (pinfunction "E_2") (pintype "passive"))
      (node (ref "Q9") (pin "2") (pinfunction "E_2") (pintype "passive"))
      (node (ref "R10") (pin "1") (pinfunction "1_1") (pintype "passive"))
      (node (ref "R3") (pin "1") (pinfunction "1_1") (pintype "passive"))
      (node (ref "T1") (pin "1") (pinfunction "1_1") (pintype "passive"))
      (node (ref "U1") (pin "1") (pinfunction "IN-_1") (pintype "passive"))
      (node (ref "U1") (pin "4") (pinfunction "OUT-_4") (pintype "passive"))
      (node (ref "U2") (pin "3") (pinfunction "VSS_3") (pintype "passive"))
      (node (ref "U3") (pin "3") (pinfunction "VSS_3") (pintype "passive"))
      (node (ref "U4") (pin "3") (pinfunction "VSS_3") (pintype "passive"))
      (node (ref "U5") (pin "3") (pinfunction "VSS_3") (pintype "passive"))
      (node (ref "U6") (pin "4") (pinfunction "GND_4") (pintype "passive"))
      (node (ref "VR1") (pin "1") (pinfunction "GND_1") (pintype "passive"))
    )
    (net (code "75") (name "Net-(BT1-+)") (class "Default")
      (node (ref "BT1") (pin "1") (pinfunction "+_1") (pintype "passive"))
      (node (ref "U15") (pin "14") (pinfunction "VBAT_14") (pintype "passive"))
    )
    (net (code "76") (name "Net-(D2-A)") (class "Default")
      (node (ref "D2") (pin "1") (pinfunction "A_1") (pintype "passive"))
      (node (ref "L1") (pin "2") (pinfunction "2_2") (pintype "passive"))
      (node (ref "Q3") (pin "2") (pinfunction "D_2") (pintype "passive"))
    )
    (net (code "77") (name "Net-(D3-PadK)") (class "Default")
      (node (ref "D3") (pin "K") (pinfunction "K_K") (pintype "passive"))
      (node (ref "R13") (pin "1") (pinfunction "1_1") (pintype "passive"))
    )
    (net (code "78") (name "Net-(D4-K)") (class "Default")
      (node (ref "D4") (pin "2") (pinfunction "K_2") (pintype "passive"))
      (node (ref "Q44") (pin "3") (pinfunction "C_3") (pintype "passive"))
      (node (ref "R19") (pin "1") (pinfunction "1_1") (pintype "passive"))
    )
    (net (code "79") (name "Net-(J8-1)") (class "Default")
      (node (ref "J8") (pin "2") (pinfunction "1_2") (pintype "passive"))
      (node (ref "Q46") (pin "3") (pinfunction "C_3") (pintype "passive"))
    )
    (net (code "80") (name "Net-(Q1-B)") (class "Default")
      (node (ref "Q1") (pin "1") (pinfunction "B_1") (pintype "passive"))
      (node (ref "R2") (pin "1") (pinfunction "1_1") (pintype "passive"))
    )
    (net (code "81") (name "Net-(Q1-C)") (class "Default")
      (node (ref "Q1") (pin "3") (pinfunction "C_3") (pintype "passive"))
      (node (ref "UP1") (pin "2") (pinfunction "2_2") (pintype "passive"))
    )
    (net (code "82") (name "Net-(Q2-B)") (class "Default")
      (node (ref "Q2") (pin "1") (pinfunction "B_1") (pintype "passive"))
      (node (ref "R9") (pin "1") (pinfunction "1_1") (pintype "passive"))
    )
    (net (code "83") (name "Net-(Q2-C)") (class "Default")
      (node (ref "Q2") (pin "3") (pinfunction "C_3") (pintype "passive"))
      (node (ref "UP2") (pin "2") (pinfunction "2_2") (pintype "passive"))
    )
    (net (code "84") (name "Net-(Q3-G)") (class "Default")
      (node (ref "Q3") (pin "1") (pinfunction "G_1") (pintype "passive"))
      (node (ref "R10") (pin "2") (pinfunction "2_2") (pintype "passive"))
      (node (ref "U6") (pin "2") (pinfunction "SE_2") (pintype "passive"))
    )
    (net (code "85") (name "Net-(Q4-C)") (class "Default")
      (node (ref "Q4") (pin "3") (pinfunction "C_3") (pintype "passive"))
      (node (ref "T6") (pin "3") (pinfunction "K'0'_3") (pintype "passive"))
    )
    (net (code "86") (name "Net-(Q5-C)") (class "Default")
      (node (ref "Q5") (pin "3") (pinfunction "C_3") (pintype "passive"))
      (node (ref "T6") (pin "4") (pinfunction "K'9'_4") (pintype "passive"))
    )
    (net (code "87") (name "Net-(Q6-C)") (class "Default")
      (node (ref "Q6") (pin "3") (pinfunction "C_3") (pintype "passive"))
      (node (ref "T6") (pin "5") (pinfunction "K'8'_5") (pintype "passive"))
    )
    (net (code "88") (name "Net-(Q7-C)") (class "Default")
      (node (ref "Q7") (pin "3") (pinfunction "C_3") (pintype "passive"))
      (node (ref "T6") (pin "6") (pinfunction "K'7'_6") (pintype "passive"))
    )
    (net (code "89") (name "Net-(Q8-C)") (class "Default")
      (node (ref "Q8") (pin "3") (pinfunction "C_3") (pintype "passive"))
      (node (ref "T6") (pin "7") (pinfunction "K'6'_7") (pintype "passive"))
    )
    (net (code "90") (name "Net-(Q9-C)") (class "Default")
      (node (ref "Q9") (pin "3") (pinfunction "C_3") (pintype "passive"))
      (node (ref "T6") (pin "9") (pinfunction "K'5'_9") (pintype "passive"))
    )
    (net (code "91") (name "Net-(Q10-C)") (class "Default")
      (node (ref "Q10") (pin "3") (pinfunction "C_3") (pintype "passive"))
      (node (ref "T6") (pin "10") (pinfunction "K'4'_10") (pintype "passive"))
    )
    (net (code "92") (name "Net-(Q11-C)") (class "Default")
      (node (ref "Q11") (pin "3") (pinfunction "C_3") (pintype "passive"))
      (node (ref "T6") (pin "11") (pinfunction "K'3'_11") (pintype "passive"))
    )
    (net (code "93") (name "Net-(Q12-C)") (class "Default")
      (node (ref "Q12") (pin "3") (pinfunction "C_3") (pintype "passive"))
      (node (ref "T6") (pin "12") (pinfunction "K'2'_12") (pintype "passive"))
    )
    (net (code "94") (name "Net-(Q13-C)") (class "Default")
      (node (ref "Q13") (pin "3") (pinfunction "C_3") (pintype "passive"))
      (node (ref "T6") (pin "13") (pinfunction "K'1'_13") (pintype "passive"))
    )
    (net (code "95") (name "Net-(Q14-C)") (class "Default")
      (node (ref "Q14") (pin "3") (pinfunction "C_3") (pintype "passive"))
      (node (ref "T7") (pin "3") (pinfunction "K'0'_3") (pintype "passive"))
    )
    (net (code "96") (name "Net-(Q15-C)") (class "Default")
      (node (ref "Q15") (pin "3") (pinfunction "C_3") (pintype "passive"))
      (node (ref "T7") (pin "4") (pinfunction "K'9'_4") (pintype "passive"))
    )
    (net (code "97") (name "Net-(Q16-C)") (class "Default")
      (node (ref "Q16") (pin "3") (pinfunction "C_3") (pintype "passive"))
      (node (ref "T7") (pin "5") (pinfunction "K'8'_5") (pintype "passive"))
    )
    (net (code "98") (name "Net-(Q17-C)") (class "Default")
      (node (ref "Q17") (pin "3") (pinfunction "C_3") (pintype "passive"))
      (node (ref "T7") (pin "6") (pinfunction "K'7'_6") (pintype "passive"))
    )
    (net (code "99") (name "Net-(Q18-C)") (class "Default")
      (node (ref "Q18") (pin "3") (pinfunction "C_3") (pintype "passive"))
      (node (ref "T7") (pin "7") (pinfunction "K'6'_7") (pintype "passive"))
    )
    (net (code "100") (name "Net-(Q19-C)") (class "Default")
      (node (ref "Q19") (pin "3") (pinfunction "C_3") (pintype "passive"))
      (node (ref "T7") (pin "9") (pinfunction "K'5'_9") (pintype "passive"))
    )
    (net (code "101") (name "Net-(Q20-C)") (class "Default")
      (node (ref "Q20") (pin "3") (pinfunction "C_3") (pintype "passive"))
      (node (ref "T7") (pin "10") (pinfunction "K'4'_10") (pintype "passive"))
    )
    (net (code "102") (name "Net-(Q21-C)") (class "Default")
      (node (ref "Q21") (pin "3") (pinfunction "C_3") (pintype "passive"))
      (node (ref "T7") (pin "11") (pinfunction "K'3'_11") (pintype "passive"))
    )
    (net (code "103") (name "Net-(Q22-C)") (class "Default")
      (node (ref "Q22") (pin "3") (pinfunction "C_3") (pintype "passive"))
      (node (ref "T7") (pin "12") (pinfunction "K'2'_12") (pintype "passive"))
    )
    (net (code "104") (name "Net-(Q23-C)") (class "Default")
      (node (ref "Q23") (pin "3") (pinfunction "C_3") (pintype "passive"))
      (node (ref "T7") (pin "13") (pinfunction "K'1'_13") (pintype "passive"))
    )
    (net (code "105") (name "Net-(Q24-C)") (class "Default")
      (node (ref "Q24") (pin "3") (pinfunction "C_3") (pintype "passive"))
      (node (ref "T8") (pin "3") (pinfunction "K'0'_3") (pintype "passive"))
    )
    (net (code "106") (name "Net-(Q25-C)") (class "Default")
      (node (ref "Q25") (pin "3") (pinfunction "C_3") (pintype "passive"))
      (node (ref "T8") (pin "4") (pinfunction "K'9'_4") (pintype "passive"))
    )
    (net (code "107") (name "Net-(Q26-C)") (class "Default")
      (node (ref "Q26") (pin "3") (pinfunction "C_3") (pintype "passive"))
      (node (ref "T8") (pin "5") (pinfunction "K'8'_5") (pintype "passive"))
    )
    (net (code "108") (name "Net-(Q27-C)") (class "Default")
      (node (ref "Q27") (pin "3") (pinfunction "C_3") (pintype "passive"))
      (node (ref "T8") (pin "6") (pinfunction "K'7'_6") (pintype "passive"))
    )
    (net (code "109") (name "Net-(Q28-C)") (class "Default")
      (node (ref "Q28") (pin "3") (pinfunction "C_3") (pintype "passive"))
      (node (ref "T8") (pin "7") (pinfunction "K'6'_7") (pintype "passive"))
    )
    (net (code "110") (name "Net-(Q29-C)") (class "Default")
      (node (ref "Q29") (pin "3") (pinfunction "C_3") (pintype "passive"))
      (node (ref "T8") (pin "9") (pinfunction "K'5'_9") (pintype "passive"))
    )
    (net (code "111") (name "Net-(Q30-C)") (class "Default")
      (node (ref "Q30") (pin "3") (pinfunction "C_3") (pintype "passive"))
      (node (ref "T8") (pin "10") (pinfunction "K'4'_10") (pintype "passive"))
    )
    (net (code "112") (name "Net-(Q31-C)") (class "Default")
      (node (ref "Q31") (pin "3") (pinfunction "C_3") (pintype "passive"))
      (node (ref "T8") (pin "11") (pinfunction "K'3'_11") (pintype "passive"))
    )
    (net (code "113") (name "Net-(Q32-C)") (class "Default")
      (node (ref "Q32") (pin "3") (pinfunction "C_3") (pintype "passive"))
      (node (ref "T8") (pin "12") (pinfunction "K'2'_12") (pintype "passive"))
    )
    (net (code "114") (name "Net-(Q33-C)") (class "Default")
      (node (ref "Q33") (pin "3") (pinfunction "C_3") (pintype "passive"))
      (node (ref "T8") (pin "13") (pinfunction "K'1'_13") (pintype "passive"))
    )
    (net (code "115") (name "Net-(Q34-C)") (class "Default")
      (node (ref "Q34") (pin "3") (pinfunction "C_3") (pintype "passive"))
      (node (ref "T9") (pin "3") (pinfunction "K'0'_3") (pintype "passive"))
    )
    (net (code "116") (name "Net-(Q35-C)") (class "Default")
      (node (ref "Q35") (pin "3") (pinfunction "C_3") (pintype "passive"))
      (node (ref "T9") (pin "4") (pinfunction "K'9'_4") (pintype "passive"))
    )
    (net (code "117") (name "Net-(Q36-C)") (class "Default")
      (node (ref "Q36") (pin "3") (pinfunction "C_3") (pintype "passive"))
      (node (ref "T9") (pin "5") (pinfunction "K'8'_5") (pintype "passive"))
    )
    (net (code "118") (name "Net-(Q37-C)") (class "Default")
      (node (ref "Q37") (pin "3") (pinfunction "C_3") (pintype "passive"))
      (node (ref "T9") (pin "6") (pinfunction "K'7'_6") (pintype "passive"))
    )
    (net (code "119") (name "Net-(Q38-C)") (class "Default")
      (node (ref "Q38") (pin "3") (pinfunction "C_3") (pintype "passive"))
      (node (ref "T9") (pin "7") (pinfunction "K'6'_7") (pintype "passive"))
    )
    (net (code "120") (name "Net-(Q39-C)") (class "Default")
      (node (ref "Q39") (pin "3") (pinfunction "C_3") (pintype "passive"))
      (node (ref "T9") (pin "9") (pinfunction "K'5'_9") (pintype "passive"))
    )
    (net (code "121") (name "Net-(Q40-C)") (class "Default")
      (node (ref "Q40") (pin "3") (pinfunction "C_3") (pintype "passive"))
      (node (ref "T9") (pin "10") (pinfunction "K'4'_10") (pintype "passive"))
    )
    (net (code "122") (name "Net-(Q41-C)") (class "Default")
      (node (ref "Q41") (pin "3") (pinfunction "C_3") (pintype "passive"))
      (node (ref "T9") (pin "11") (pinfunction "K'3'_11") (pintype "passive"))
    )
    (net (code "123") (name "Net-(Q42-C)") (class "Default")
      (node (ref "Q42") (pin "3") (pinfunction "C_3") (pintype "passive"))
      (node (ref "T9") (pin "12") (pinfunction "K'2'_12") (pintype "passive"))
    )
    (net (code "124") (name "Net-(Q43-C)") (class "Default")
      (node (ref "Q43") (pin "3") (pinfunction "C_3") (pintype "passive"))
      (node (ref "T9") (pin "13") (pinfunction "K'1'_13") (pintype "passive"))
    )
    (net (code "125") (name "Net-(Q44-B)") (class "Default")
      (node (ref "Q44") (pin "1") (pinfunction "B_1") (pintype "passive"))
      (node (ref "R20") (pin "2") (pinfunction "2_2") (pintype "passive"))
    )
    (net (code "126") (name "Net-(Q44-E)") (class "Default")
      (node (ref "Q44") (pin "2") (pinfunction "E_2") (pintype "passive"))
      (node (ref "R28") (pin "1") (pinfunction "1_1") (pintype "passive"))
      (node (ref "U8") (pin "14") (pinfunction "RI#_14") (pintype "passive"))
    )
    (net (code "127") (name "Net-(Q45-B)") (class "Default")
      (node (ref "Q45") (pin "1") (pinfunction "B_1") (pintype "passive"))
      (node (ref "R28") (pin "2") (pinfunction "2_2") (pintype "passive"))
    )
    (net (code "128") (name "Net-(Q45-C)") (class "Default")
      (node (ref "Q45") (pin "3") (pinfunction "C_3") (pintype "passive"))
      (node (ref "R60") (pin "2") (pinfunction "2_2") (pintype "passive"))
    )
    (net (code "129") (name "Net-(Q46-B)") (class "Default")
      (node (ref "Q46") (pin "1") (pinfunction "B_1") (pintype "passive"))
      (node (ref "R74") (pin "2") (pinfunction "2_2") (pintype "passive"))
    )
    (net (code "130") (name "Net-(R5-Pad1)") (class "Default")
      (node (ref "R5") (pin "1") (pinfunction "1_1") (pintype "passive"))
      (node (ref "UP1") (pin "1") (pinfunction "1_1") (pintype "passive"))
    )
    (net (code "131") (name "Net-(R7-BOT)") (class "Default")
      (node (ref "R4") (pin "2") (pinfunction "2_2") (pintype "passive"))
      (node (ref "R7") (pin "3") (pinfunction "BOT_3") (pintype "passive"))
    )
    (net (code "132") (name "Net-(R11-Pad1)") (class "Default")
      (node (ref "R11") (pin "1") (pinfunction "1_1") (pintype "passive"))
      (node (ref "UP2") (pin "1") (pinfunction "1_1") (pintype "passive"))
    )
    (net (code "133") (name "Net-(T6-Anode)") (class "Default")
      (node (ref "R8") (pin "1") (pinfunction "1_1") (pintype "passive"))
      (node (ref "T6") (pin "2") (pinfunction "Anode_2") (pintype "passive"))
    )
    (net (code "134") (name "Net-(T7-Anode)") (class "Default")
      (node (ref "R6") (pin "1") (pinfunction "1_1") (pintype "passive"))
      (node (ref "T7") (pin "2") (pinfunction "Anode_2") (pintype "passive"))
    )
    (net (code "135") (name "Net-(T8-Anode)") (class "Default")
      (node (ref "R15") (pin "1") (pinfunction "1_1") (pintype "passive"))
      (node (ref "T8") (pin "2") (pinfunction "Anode_2") (pintype "passive"))
    )
    (net (code "136") (name "Net-(T9-Anode)") (class "Default")
      (node (ref "R16") (pin "1") (pinfunction "1_1") (pintype "passive"))
      (node (ref "T9") (pin "2") (pinfunction "Anode_2") (pintype "passive"))
    )
    (net (code "137") (name "Net-(U2-DO)") (class "Default")
      (node (ref "U2") (pin "2") (pinfunction "DO_2") (pintype "passive"))
      (node (ref "U3") (pin "4") (pinfunction "DI_4") (pintype "passive"))
    )
    (net (code "138") (name "Net-(U3-DO)") (class "Default")
      (node (ref "U3") (pin "2") (pinfunction "DO_2") (pintype "passive"))
      (node (ref "U4") (pin "4") (pinfunction "DI_4") (pintype "passive"))
    )
    (net (code "139") (name "Net-(U4-DO)") (class "Default")
      (node (ref "U4") (pin "2") (pinfunction "DO_2") (pintype "passive"))
      (node (ref "U5") (pin "4") (pinfunction "DI_4") (pintype "passive"))
    )
    (net (code "140") (name "Net-(U6-FB)") (class "Default")
      (node (ref "C8") (pin "2") (pinfunction "2_2") (pintype "passive"))
      (node (ref "R3") (pin "2") (pinfunction "2_2") (pintype "passive"))
      (node (ref "R4") (pin "1") (pinfunction "1_1") (pintype "passive"))
      (node (ref "U6") (pin "5") (pinfunction "FB_5") (pintype "passive"))
    )
    (net (code "141") (name "Net-(U6-TC)") (class "Default")
      (node (ref "C9") (pin "1") (pinfunction "1_1") (pintype "passive"))
      (node (ref "U6") (pin "3") (pinfunction "TC_3") (pintype "passive"))
    )
    (net (code "142") (name "Net-(U7A-PD0-OSC_IN)") (class "Default")
      (node (ref "C13") (pin "2") (pinfunction "2_2") (pintype "passive"))
      (node (ref "U7") (pin "5") (pinfunction "PD0-OSC_IN_5") (pintype "bidirectional"))
      (node (ref "Y1") (pin "1") (pinfunction "OSC1_1") (pintype "passive"))
    )
    (net (code "143") (name "Net-(U7A-PD1)") (class "Default")
      (node (ref "C14") (pin "2") (pinfunction "2_2") (pintype "passive"))
      (node (ref "U7") (pin "6") (pinfunction "PD1_6") (pintype "bidirectional"))
      (node (ref "Y1") (pin "2") (pinfunction "OSC2_2") (pintype "passive"))
    )
    (net (code "144") (name "Net-(U8-DCD#)") (class "Default")
      (node (ref "R20") (pin "1") (pinfunction "1_1") (pintype "passive"))
      (node (ref "U8") (pin "13") (pinfunction "DCD#_13") (pintype "passive"))
    )
    (net (code "145") (name "Net-(U8-V3.3)") (class "Default")
      (node (ref "C24") (pin "1") (pinfunction "1_1") (pintype "passive"))
      (node (ref "U8") (pin "4") (pinfunction "V3.3_4") (pintype "passive"))
    )
    (net (code "146") (name "Net-(U8-XI)") (class "Default")
      (node (ref "C25") (pin "1") (pinfunction "1_1") (pintype "passive"))
      (node (ref "U8") (pin "7") (pinfunction "XI_7") (pintype "passive"))
      (node (ref "Y2") (pin "1") (pinfunction "OSC1_1") (pintype "passive"))
    )
    (net (code "147") (name "Net-(U8-XO)") (class "Default")
      (node (ref "C26") (pin "1") (pinfunction "1_1") (pintype "passive"))
      (node (ref "U8") (pin "8") (pinfunction "XO_8") (pintype "passive"))
      (node (ref "Y2") (pin "2") (pinfunction "OSC2_2") (pintype "passive"))
    )
    (net (code "148") (name "Net-(U9-QA)") (class "Default")
      (node (ref "R22") (pin "1") (pinfunction "1_1") (pintype "passive"))
      (node (ref "U9") (pin "15") (pinfunction "QA_15") (pintype "tri_state"))
    )
    (net (code "149") (name "Net-(U9-QB)") (class "Default")
      (node (ref "R29") (pin "1") (pinfunction "1_1") (pintype "passive"))
      (node (ref "U9") (pin "1") (pinfunction "QB_1") (pintype "tri_state"))
    )
    (net (code "150") (name "Net-(U9-QC)") (class "Default")
      (node (ref "R34") (pin "1") (pinfunction "1_1") (pintype "passive"))
      (node (ref "U9") (pin "2") (pinfunction "QC_2") (pintype "tri_state"))
    )
    (net (code "151") (name "Net-(U9-QD)") (class "Default")
      (node (ref "R40") (pin "1") (pinfunction "1_1") (pintype "passive"))
      (node (ref "U9") (pin "3") (pinfunction "QD_3") (pintype "tri_state"))
    )
    (net (code "152") (name "Net-(U9-QE)") (class "Default")
      (node (ref "R45") (pin "1") (pinfunction "1_1") (pintype "passive"))
      (node (ref "U9") (pin "4") (pinfunction "QE_4") (pintype "tri_state"))
    )
    (net (code "153") (name "Net-(U9-QF)") (class "Default")
      (node (ref "R50") (pin "1") (pinfunction "1_1") (pintype "passive"))
      (node (ref "U9") (pin "5") (pinfunction "QF_5") (pintype "tri_state"))
    )
    (net (code "154") (name "Net-(U9-QG)") (class "Default")
      (node (ref "R55") (pin "1") (pinfunction "1_1") (pintype "passive"))
      (node (ref "U9") (pin "6") (pinfunction "QG_6") (pintype "tri_state"))
    )
    (net (code "155") (name "Net-(U9-QH)") (class "Default")
      (node (ref "R61") (pin "1") (pinfunction "1_1") (pintype "passive"))
      (node (ref "U9") (pin "7") (pinfunction "QH_7") (pintype "tri_state"))
    )
    (net (code "156") (name "Net-(U10-QA)") (class "Default")
      (node (ref "R23") (pin "1") (pinfunction "1_1") (pintype "passive"))
      (node (ref "U10") (pin "15") (pinfunction "QA_15") (pintype "tri_state"))
    )
    (net (code "157") (name "Net-(U10-QB)") (class "Default")
      (node (ref "R30") (pin "1") (pinfunction "1_1") (pintype "passive"))
      (node (ref "U10") (pin "1") (pinfunction "QB_1") (pintype "tri_state"))
    )
    (net (code "158") (name "Net-(U10-QC)") (class "Default")
      (node (ref "R35") (pin "1") (pinfunction "1_1") (pintype "passive"))
      (node (ref "U10") (pin "2") (pinfunction "QC_2") (pintype "tri_state"))
    )
    (net (code "159") (name "Net-(U10-QD)") (class "Default")
      (node (ref "R41") (pin "1") (pinfunction "1_1") (pintype "passive"))
      (node (ref "U10") (pin "3") (pinfunction "QD_3") (pintype "tri_state"))
    )
    (net (code "160") (name "Net-(U10-QE)") (class "Default")
      (node (ref "R46") (pin "1") (pinfunction "1_1") (pintype "passive"))
      (node (ref "U10") (pin "4") (pinfunction "QE_4") (pintype "tri_state"))
    )
    (net (code "161") (name "Net-(U10-QF)") (class "Default")
      (node (ref "R51") (pin "1") (pinfunction "1_1") (pintype "passive"))
      (node (ref "U10") (pin "5") (pinfunction "QF_5") (pintype "tri_state"))
    )
    (net (code "162") (name "Net-(U10-QG)") (class "Default")
      (node (ref "R56") (pin "1") (pinfunction "1_1") (pintype "passive"))
      (node (ref "U10") (pin "6") (pinfunction "QG_6") (pintype "tri_state"))
    )
    (net (code "163") (name "Net-(U10-QH')") (class "Default")
      (node (ref "U10") (pin "9") (pinfunction "QH'_9") (pintype "output"))
      (node (ref "U11") (pin "14") (pinfunction "SER_14") (pintype "input"))
    )
    (net (code "164") (name "Net-(U10-QH)") (class "Default")
      (node (ref "R62") (pin "1") (pinfunction "1_1") (pintype "passive"))
      (node (ref "U10") (pin "7") (pinfunction "QH_7") (pintype "tri_state"))
    )
    (net (code "165") (name "Net-(U10-SER)") (class "Default")
      (node (ref "U10") (pin "14") (pinfunction "SER_14") (pintype "input"))
      (node (ref "U9") (pin "9") (pinfunction "QH'_9") (pintype "output"))
    )
    (net (code "166") (name "Net-(U11-QA)") (class "Default")
      (node (ref "R24") (pin "1") (pinfunction "1_1") (pintype "passive"))
      (node (ref "U11") (pin "15") (pinfunction "QA_15") (pintype "tri_state"))
    )
    (net (code "167") (name "Net-(U11-QB)") (class "Default")
      (node (ref "R31") (pin "1") (pinfunction "1_1") (pintype "passive"))
      (node (ref "U11") (pin "1") (pinfunction "QB_1") (pintype "tri_state"))
    )
    (net (code "168") (name "Net-(U11-QC)") (class "Default")
      (node (ref "R36") (pin "1") (pinfunction "1_1") (pintype "passive"))
      (node (ref "U11") (pin "2") (pinfunction "QC_2") (pintype "tri_state"))
    )
    (net (code "169") (name "Net-(U11-QD)") (class "Default")
      (node (ref "R42") (pin "1") (pinfunction "1_1") (pintype "passive"))
      (node (ref "U11") (pin "3") (pinfunction "QD_3") (pintype "tri_state"))
    )
    (net (code "170") (name "Net-(U11-QE)") (class "Default")
      (node (ref "R47") (pin "1") (pinfunction "1_1") (pintype "passive"))
      (node (ref "U11") (pin "4") (pinfunction "QE_4") (pintype "tri_state"))
    )
    (net (code "171") (name "Net-(U11-QF)") (class "Default")
      (node (ref "R52") (pin "1") (pinfunction "1_1") (pintype "passive"))
      (node (ref "U11") (pin "5") (pinfunction "QF_5") (pintype "tri_state"))
    )
    (net (code "172") (name "Net-(U11-QG)") (class "Default")
      (node (ref "R57") (pin "1") (pinfunction "1_1") (pintype "passive"))
      (node (ref "U11") (pin "6") (pinfunction "QG_6") (pintype "tri_state"))
    )
    (net (code "173") (name "Net-(U11-QH')") (class "Default")
      (node (ref "U11") (pin "9") (pinfunction "QH'_9") (pintype "output"))
      (node (ref "U12") (pin "14") (pinfunction "SER_14") (pintype "input"))
    )
    (net (code "174") (name "Net-(U11-QH)") (class "Default")
      (node (ref "R63") (pin "1") (pinfunction "1_1") (pintype "passive"))
      (node (ref "U11") (pin "7") (pinfunction "QH_7") (pintype "tri_state"))
    )
    (net (code "175") (name "Net-(U12-QA)") (class "Default")
      (node (ref "R25") (pin "1") (pinfunction "1_1") (pintype "passive"))
      (node (ref "U12") (pin "15") (pinfunction "QA_15") (pintype "tri_state"))
    )
    (net (code "176") (name "Net-(U12-QB)") (class "Default")
      (node (ref "R32") (pin "1") (pinfunction "1_1") (pintype "passive"))
      (node (ref "U12") (pin "1") (pinfunction "QB_1") (pintype "tri_state"))
    )
    (net (code "177") (name "Net-(U12-QC)") (class "Default")
      (node (ref "R37") (pin "1") (pinfunction "1_1") (pintype "passive"))
      (node (ref "U12") (pin "2") (pinfunction "QC_2") (pintype "tri_state"))
    )
    (net (code "178") (name "Net-(U12-QD)") (class "Default")
      (node (ref "R43") (pin "1") (pinfunction "1_1") (pintype "passive"))
      (node (ref "U12") (pin "3") (pinfunction "QD_3") (pintype "tri_state"))
    )
    (net (code "179") (name "Net-(U12-QE)") (class "Default")
      (node (ref "R48") (pin "1") (pinfunction "1_1") (pintype "passive"))
      (node (ref "U12") (pin "4") (pinfunction "QE_4") (pintype "tri_state"))
    )
    (net (code "180") (name "Net-(U12-QF)") (class "Default")
      (node (ref "R53") (pin "1") (pinfunction "1_1") (pintype "passive"))
      (node (ref "U12") (pin "5") (pinfunction "QF_5") (pintype "tri_state"))
    )
    (net (code "181") (name "Net-(U12-QG)") (class "Default")
      (node (ref "R58") (pin "1") (pinfunction "1_1") (pintype "passive"))
      (node (ref "U12") (pin "6") (pinfunction "QG_6") (pintype "tri_state"))
    )
    (net (code "182") (name "Net-(U12-QH')") (class "Default")
      (node (ref "U12") (pin "9") (pinfunction "QH'_9") (pintype "output"))
      (node (ref "U13") (pin "14") (pinfunction "SER_14") (pintype "input"))
    )
    (net (code "183") (name "Net-(U12-QH)") (class "Default")
      (node (ref "R64") (pin "1") (pinfunction "1_1") (pintype "passive"))
      (node (ref "U12") (pin "7") (pinfunction "QH_7") (pintype "tri_state"))
    )
    (net (code "184") (name "Net-(U13-QA)") (class "Default")
      (node (ref "R26") (pin "1") (pinfunction "1_1") (pintype "passive"))
      (node (ref "U13") (pin "15") (pinfunction "QA_15") (pintype "tri_state"))
    )
    (net (code "185") (name "Net-(U13-QB)") (class "Default")
      (node (ref "R33") (pin "1") (pinfunction "1_1") (pintype "passive"))
      (node (ref "U13") (pin "1") (pinfunction "QB_1") (pintype "tri_state"))
    )
    (net (code "186") (name "Net-(U13-QC)") (class "Default")
      (node (ref "R38") (pin "1") (pinfunction "1_1") (pintype "passive"))
      (node (ref "U13") (pin "2") (pinfunction "QC_2") (pintype "tri_state"))
    )
    (net (code "187") (name "Net-(U13-QD)") (class "Default")
      (node (ref "R44") (pin "1") (pinfunction "1_1") (pintype "passive"))
      (node (ref "U13") (pin "3") (pinfunction "QD_3") (pintype "tri_state"))
    )
    (net (code "188") (name "Net-(U13-QE)") (class "Default")
      (node (ref "R49") (pin "1") (pinfunction "1_1") (pintype "passive"))
      (node (ref "U13") (pin "4") (pinfunction "QE_4") (pintype "tri_state"))
    )
    (net (code "189") (name "Net-(U13-QF)") (class "Default")
      (node (ref "R54") (pin "1") (pinfunction "1_1") (pintype "passive"))
      (node (ref "U13") (pin "5") (pinfunction "QF_5") (pintype "tri_state"))
    )
    (net (code "190") (name "Net-(U13-QG)") (class "Default")
      (node (ref "R59") (pin "1") (pinfunction "1_1") (pintype "passive"))
      (node (ref "U13") (pin "6") (pinfunction "QG_6") (pintype "tri_state"))
    )
    (net (code "191") (name "Net-(U13-QH)") (class "Default")
      (node (ref "R65") (pin "1") (pinfunction "1_1") (pintype "passive"))
      (node (ref "U13") (pin "7") (pinfunction "QH_7") (pintype "tri_state"))
    )
    (net (code "192") (name "VH") (class "Default")
      (node (ref "C10") (pin "1") (pinfunction "1_1") (pintype "passive"))
      (node (ref "D2") (pin "2") (pinfunction "K_2") (pintype "passive"))
      (node (ref "J2") (pin "1") (pinfunction "1_1") (pintype "passive"))
      (node (ref "R11") (pin "2") (pinfunction "2_2") (pintype "passive"))
      (node (ref "R15") (pin "2") (pinfunction "2_2") (pintype "passive"))
      (node (ref "R16") (pin "2") (pinfunction "2_2") (pintype "passive"))
      (node (ref "R5") (pin "2") (pinfunction "2_2") (pintype "passive"))
      (node (ref "R6") (pin "2") (pinfunction "2_2") (pintype "passive"))
      (node (ref "R7") (pin "1") (pinfunction "TOP_1") (pintype "passive"))
      (node (ref "R7") (pin "2") (pinfunction "TAP_2") (pintype "passive"))
      (node (ref "R8") (pin "2") (pinfunction "2_2") (pintype "passive"))
    )
    (net (code "193") (name "unconnected-(T6-NC-Pad1)") (class "Default")
      (node (ref "T6") (pin "1") (pinfunction "NC_1") (pintype "passive"))
    )
    (net (code "194") (name "unconnected-(T6-NC-Pad8)") (class "Default")
      (node (ref "T6") (pin "8") (pinfunction "NC_8") (pintype "passive"))
    )
    (net (code "195") (name "unconnected-(T7-NC-Pad1)") (class "Default")
      (node (ref "T7") (pin "1") (pinfunction "NC_1") (pintype "passive"))
    )
    (net (code "196") (name "unconnected-(T7-NC-Pad8)") (class "Default")
      (node (ref "T7") (pin "8") (pinfunction "NC_8") (pintype "passive"))
    )
    (net (code "197") (name "unconnected-(T8-NC-Pad1)") (class "Default")
      (node (ref "T8") (pin "1") (pinfunction "NC_1") (pintype "passive"))
    )
    (net (code "198") (name "unconnected-(T8-NC-Pad8)") (class "Default")
      (node (ref "T8") (pin "8") (pinfunction "NC_8") (pintype "passive"))
    )
    (net (code "199") (name "unconnected-(T9-NC-Pad1)") (class "Default")
      (node (ref "T9") (pin "1") (pinfunction "NC_1") (pintype "passive"))
    )
    (net (code "200") (name "unconnected-(T9-NC-Pad8)") (class "Default")
      (node (ref "T9") (pin "8") (pinfunction "NC_8") (pintype "passive"))
    )
    (net (code "201") (name "unconnected-(U5-DO-Pad2)") (class "Default")
      (node (ref "U5") (pin "2") (pinfunction "DO_2") (pintype "passive"))
    )
    (net (code "202") (name "unconnected-(U7A-PA4-Pad20)") (class "Default")
      (node (ref "U7") (pin "20") (pinfunction "PA4_20") (pintype "bidirectional"))
    )
    (net (code "203") (name "unconnected-(U7A-PA5-Pad21)") (class "Default")
      (node (ref "U7") (pin "21") (pinfunction "PA5_21") (pintype "bidirectional"))
    )
    (net (code "204") (name "unconnected-(U7A-PA8-Pad41)") (class "Default")
      (node (ref "U7") (pin "41") (pinfunction "PA8_41") (pintype "bidirectional"))
    )
    (net (code "205") (name "unconnected-(U7A-PA11-Pad44)") (class "Default")
      (node (ref "U7") (pin "44") (pinfunction "PA11_44") (pintype "bidirectional"))
    )
    (net (code "206") (name "unconnected-(U7A-PB1-Pad27)") (class "Default")
      (node (ref "U7") (pin "27") (pinfunction "PB1_27") (pintype "bidirectional"))
    )
    (net (code "207") (name "unconnected-(U7A-PB5-Pad57)") (class "Default")
      (node (ref "U7") (pin "57") (pinfunction "PB5_57") (pintype "bidirectional"))
    )
    (net (code "208") (name "unconnected-(U7A-PB9-Pad62)") (class "Default")
      (node (ref "U7") (pin "62") (pinfunction "PB9_62") (pintype "bidirectional"))
    )
    (net (code "209") (name "unconnected-(U7A-PB12-Pad33)") (class "Default")
      (node (ref "U7") (pin "33") (pinfunction "PB12_33") (pintype "bidirectional"))
    )
    (net (code "210") (name "unconnected-(U7A-PB13-Pad34)") (class "Default")
      (node (ref "U7") (pin "34") (pinfunction "PB13_34") (pintype "bidirectional"))
    )
    (net (code "211") (name "unconnected-(U7A-PB14-Pad35)") (class "Default")
      (node (ref "U7") (pin "35") (pinfunction "PB14_35") (pintype "bidirectional"))
    )
    (net (code "212") (name "unconnected-(U7A-PB15-Pad36)") (class "Default")
      (node (ref "U7") (pin "36") (pinfunction "PB15_36") (pintype "bidirectional"))
    )
    (net (code "213") (name "unconnected-(U7A-PC0-Pad8)") (class "Default")
      (node (ref "U7") (pin "8") (pinfunction "PC0_8") (pintype "bidirectional"))
    )
    (net (code "214") (name "unconnected-(U7A-PC1-Pad9)") (class "Default")
      (node (ref "U7") (pin "9") (pinfunction "PC1_9") (pintype "bidirectional"))
    )
    (net (code "215") (name "unconnected-(U7A-PC2-Pad10)") (class "Default")
      (node (ref "U7") (pin "10") (pinfunction "PC2_10") (pintype "bidirectional"))
    )
    (net (code "216") (name "unconnected-(U7A-PC3-Pad11)") (class "Default")
      (node (ref "U7") (pin "11") (pinfunction "PC3_11") (pintype "bidirectional"))
    )
    (net (code "217") (name "unconnected-(U7A-PC4-Pad24)") (class "Default")
      (node (ref "U7") (pin "24") (pinfunction "PC4_24") (pintype "bidirectional"))
    )
    (net (code "218") (name "unconnected-(U7A-PC5-Pad25)") (class "Default")
      (node (ref "U7") (pin "25") (pinfunction "PC5_25") (pintype "bidirectional"))
    )
    (net (code "219") (name "unconnected-(U7A-PC6-Pad37)") (class "Default")
      (node (ref "U7") (pin "37") (pinfunction "PC6_37") (pintype "bidirectional"))
    )
    (net (code "220") (name "unconnected-(U7A-PC7-Pad38)") (class "Default")
      (node (ref "U7") (pin "38") (pinfunction "PC7_38") (pintype "bidirectional"))
    )
    (net (code "221") (name "unconnected-(U7A-PC8-Pad39)") (class "Default")
      (node (ref "U7") (pin "39") (pinfunction "PC8_39") (pintype "bidirectional"))
    )
    (net (code "222") (name "unconnected-(U7A-PC9-Pad40)") (class "Default")
      (node (ref "U7") (pin "40") (pinfunction "PC9_40") (pintype "bidirectional"))
    )
    (net (code "223") (name "unconnected-(U7A-PC13-TAMPER-RTC-Pad2)") (class "Default")
      (node (ref "U7") (pin "2") (pinfunction "PC13-TAMPER-RTC_2") (pintype "bidirectional"))
    )
    (net (code "224") (name "unconnected-(U7A-PC14-OSC32_IN-Pad3)") (class "Default")
      (node (ref "U7") (pin "3") (pinfunction "PC14-OSC32_IN_3") (pintype "bidirectional"))
    )
    (net (code "225") (name "unconnected-(U7A-PC15-OSC32_OUT-Pad4)") (class "Default")
      (node (ref "U7") (pin "4") (pinfunction "PC15-OSC32_OUT_4") (pintype "bidirectional"))
    )
    (net (code "226") (name "unconnected-(U8-CTS#-Pad9)") (class "Default")
      (node (ref "U8") (pin "9") (pinfunction "CTS#_9") (pintype "passive"))
    )
    (net (code "227") (name "unconnected-(U8-DSR#-Pad10)") (class "Default")
      (node (ref "U8") (pin "10") (pinfunction "DSR#_10") (pintype "passive"))
    )
    (net (code "228") (name "unconnected-(U8-DTR#-Pad12)") (class "Default")
      (node (ref "U8") (pin "12") (pinfunction "DTR#_12") (pintype "passive"))
    )
    (net (code "229") (name "unconnected-(U8-R232-Pad15)") (class "Default")
      (node (ref "U8") (pin "15") (pinfunction "R232_15") (pintype "passive"))
    )
    (net (code "230") (name "unconnected-(U8-RTS#-Pad11)") (class "Default")
      (node (ref "U8") (pin "11") (pinfunction "RTS#_11") (pintype "passive"))
    )
    (net (code "231") (name "unconnected-(U13-QH'-Pad9)") (class "Default")
      (node (ref "U13") (pin "9") (pinfunction "QH'_9") (pintype "output"))
    )
    (net (code "232") (name "unconnected-(U15-32KHZ-Pad1)") (class "Default")
      (node (ref "U15") (pin "1") (pinfunction "32KHZ_1") (pintype "passive"))
    )
    (net (code "233") (name "unconnected-(U15-~{RST}-Pad4)") (class "Default")
      (node (ref "U15") (pin "4") (pinfunction "~{RST}_4") (pintype "passive"))
    )
  )
)
